# NN22_VCCS_SrcAdapter02_s00.net
KiCad netlist of a schematic drawn in EAGLE
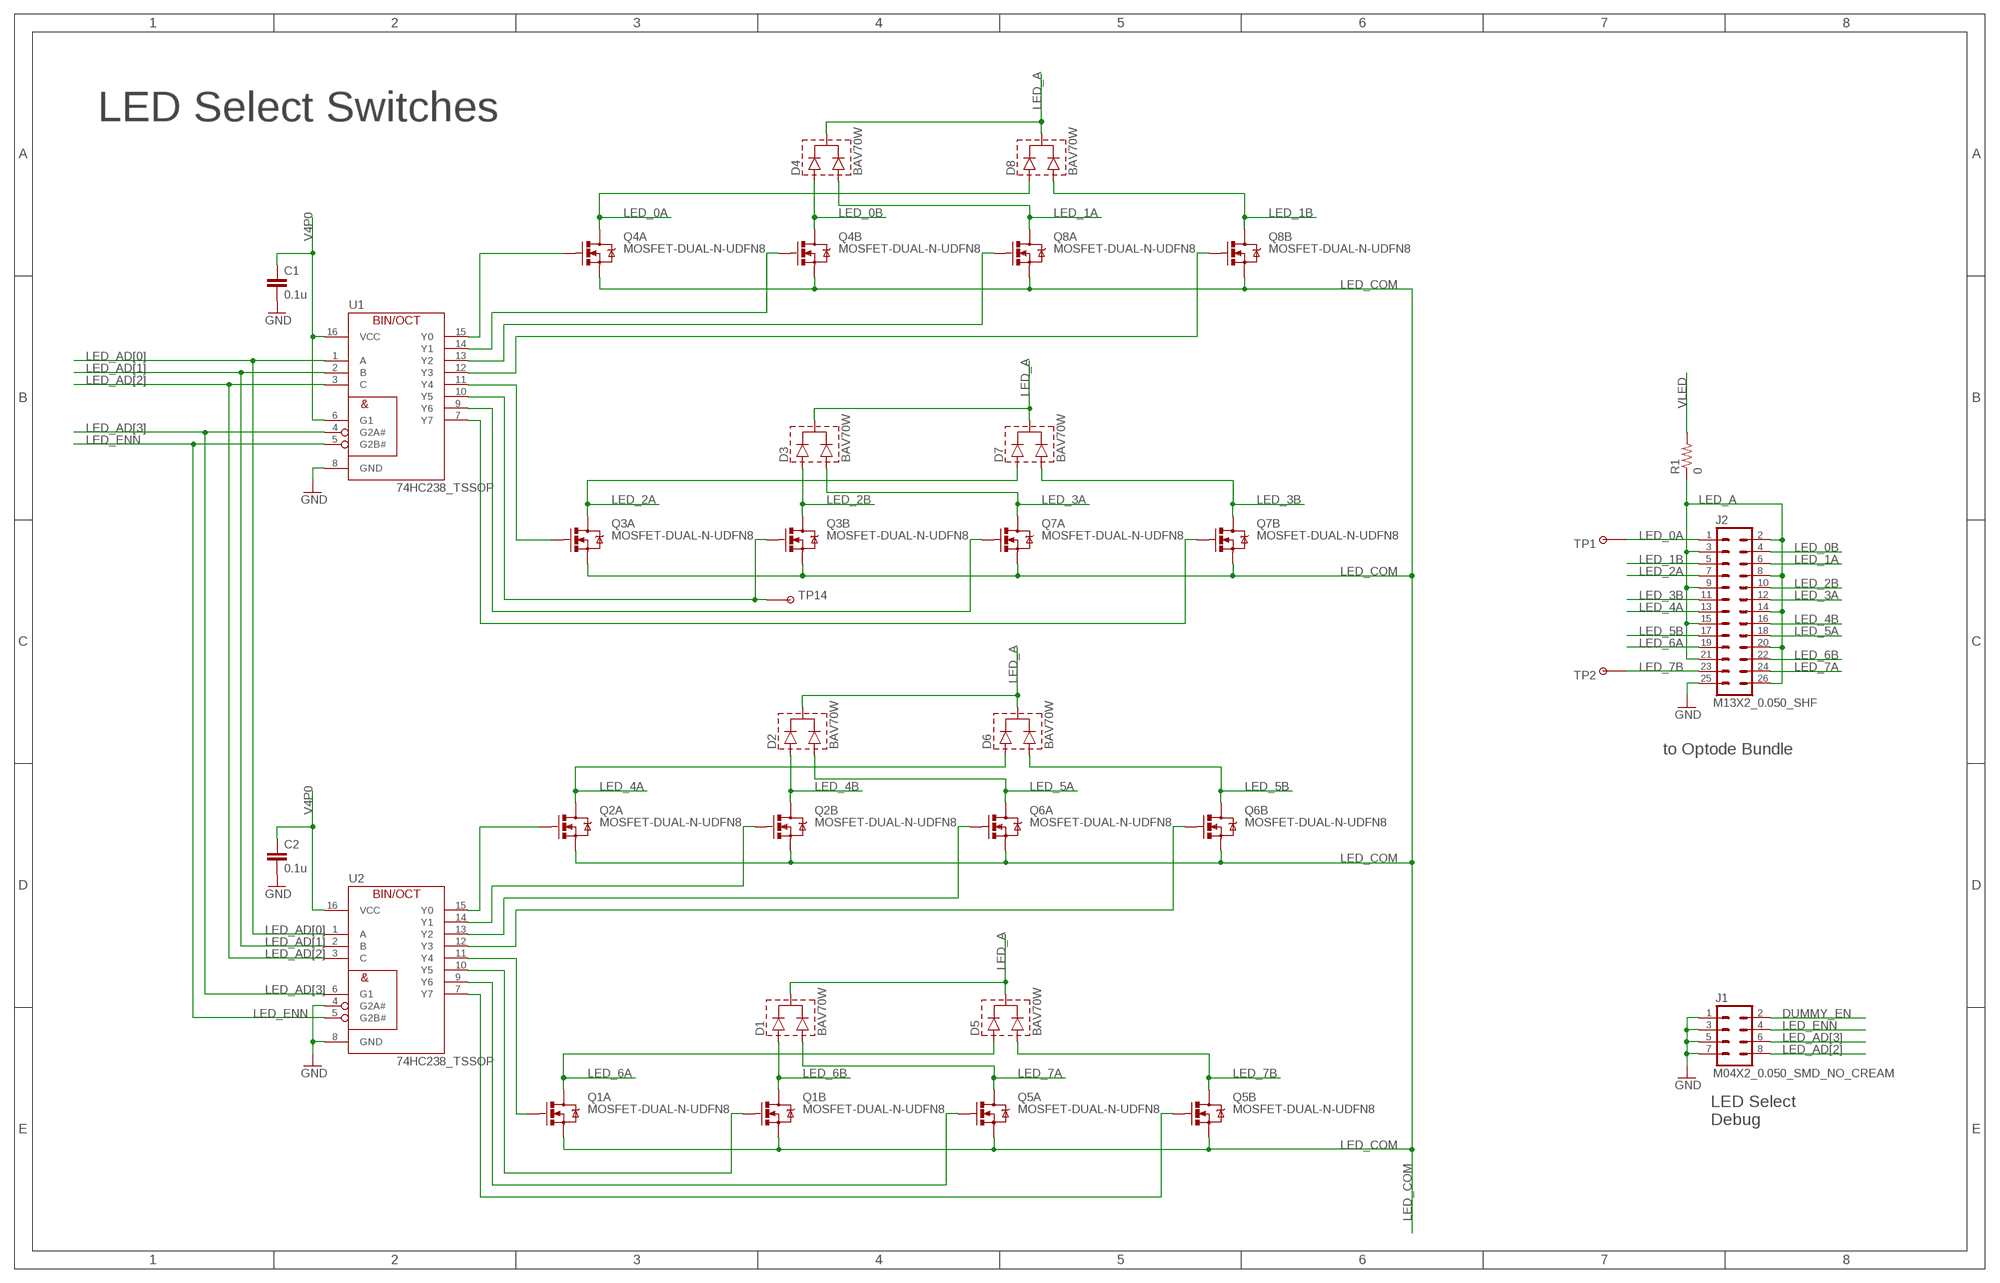
[diagram p0: schematic, sheet 1]
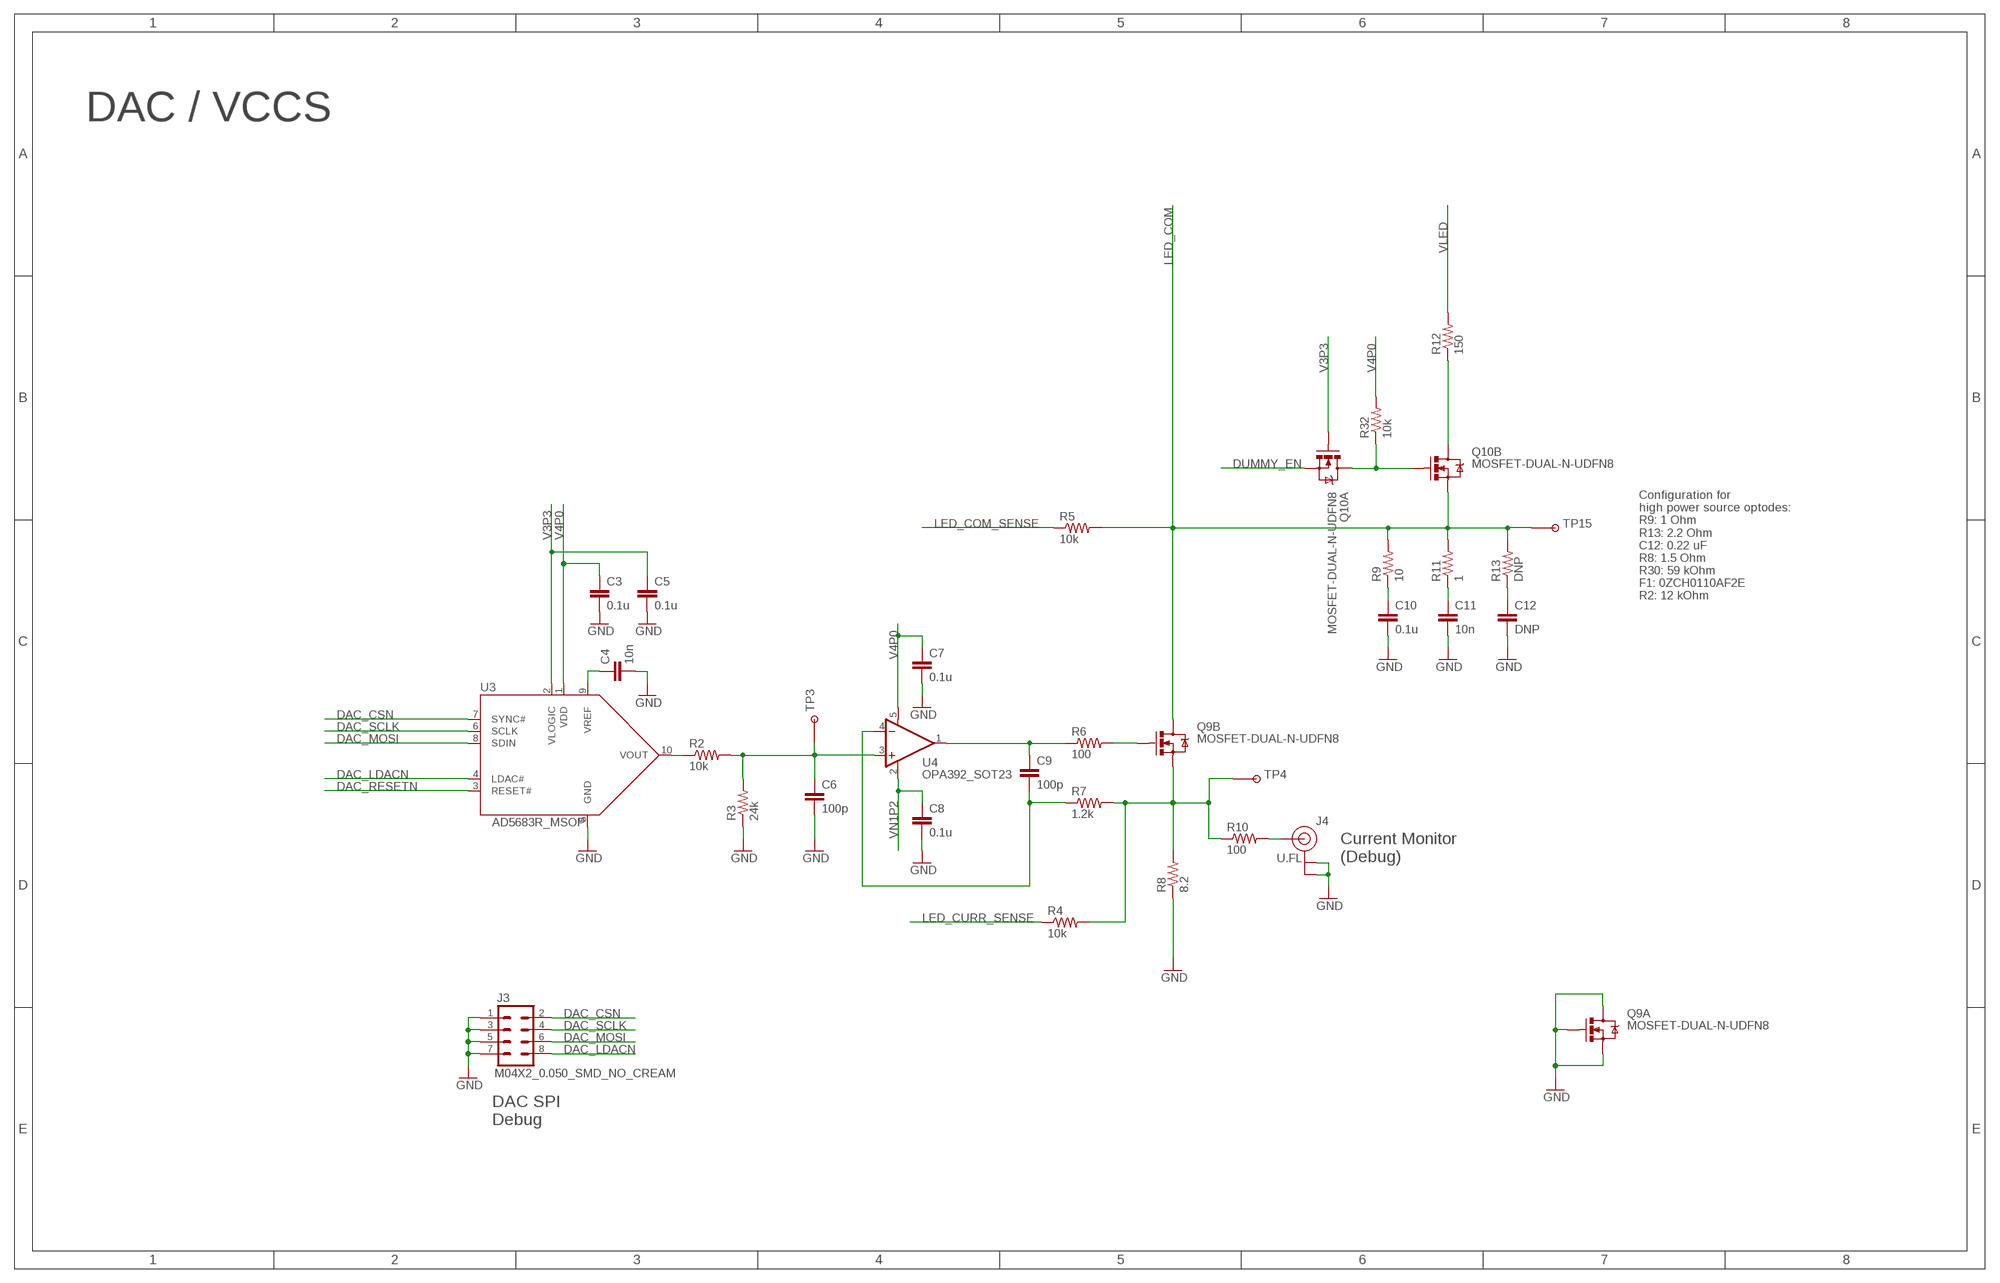
[diagram p1: schematic, sheet 2]
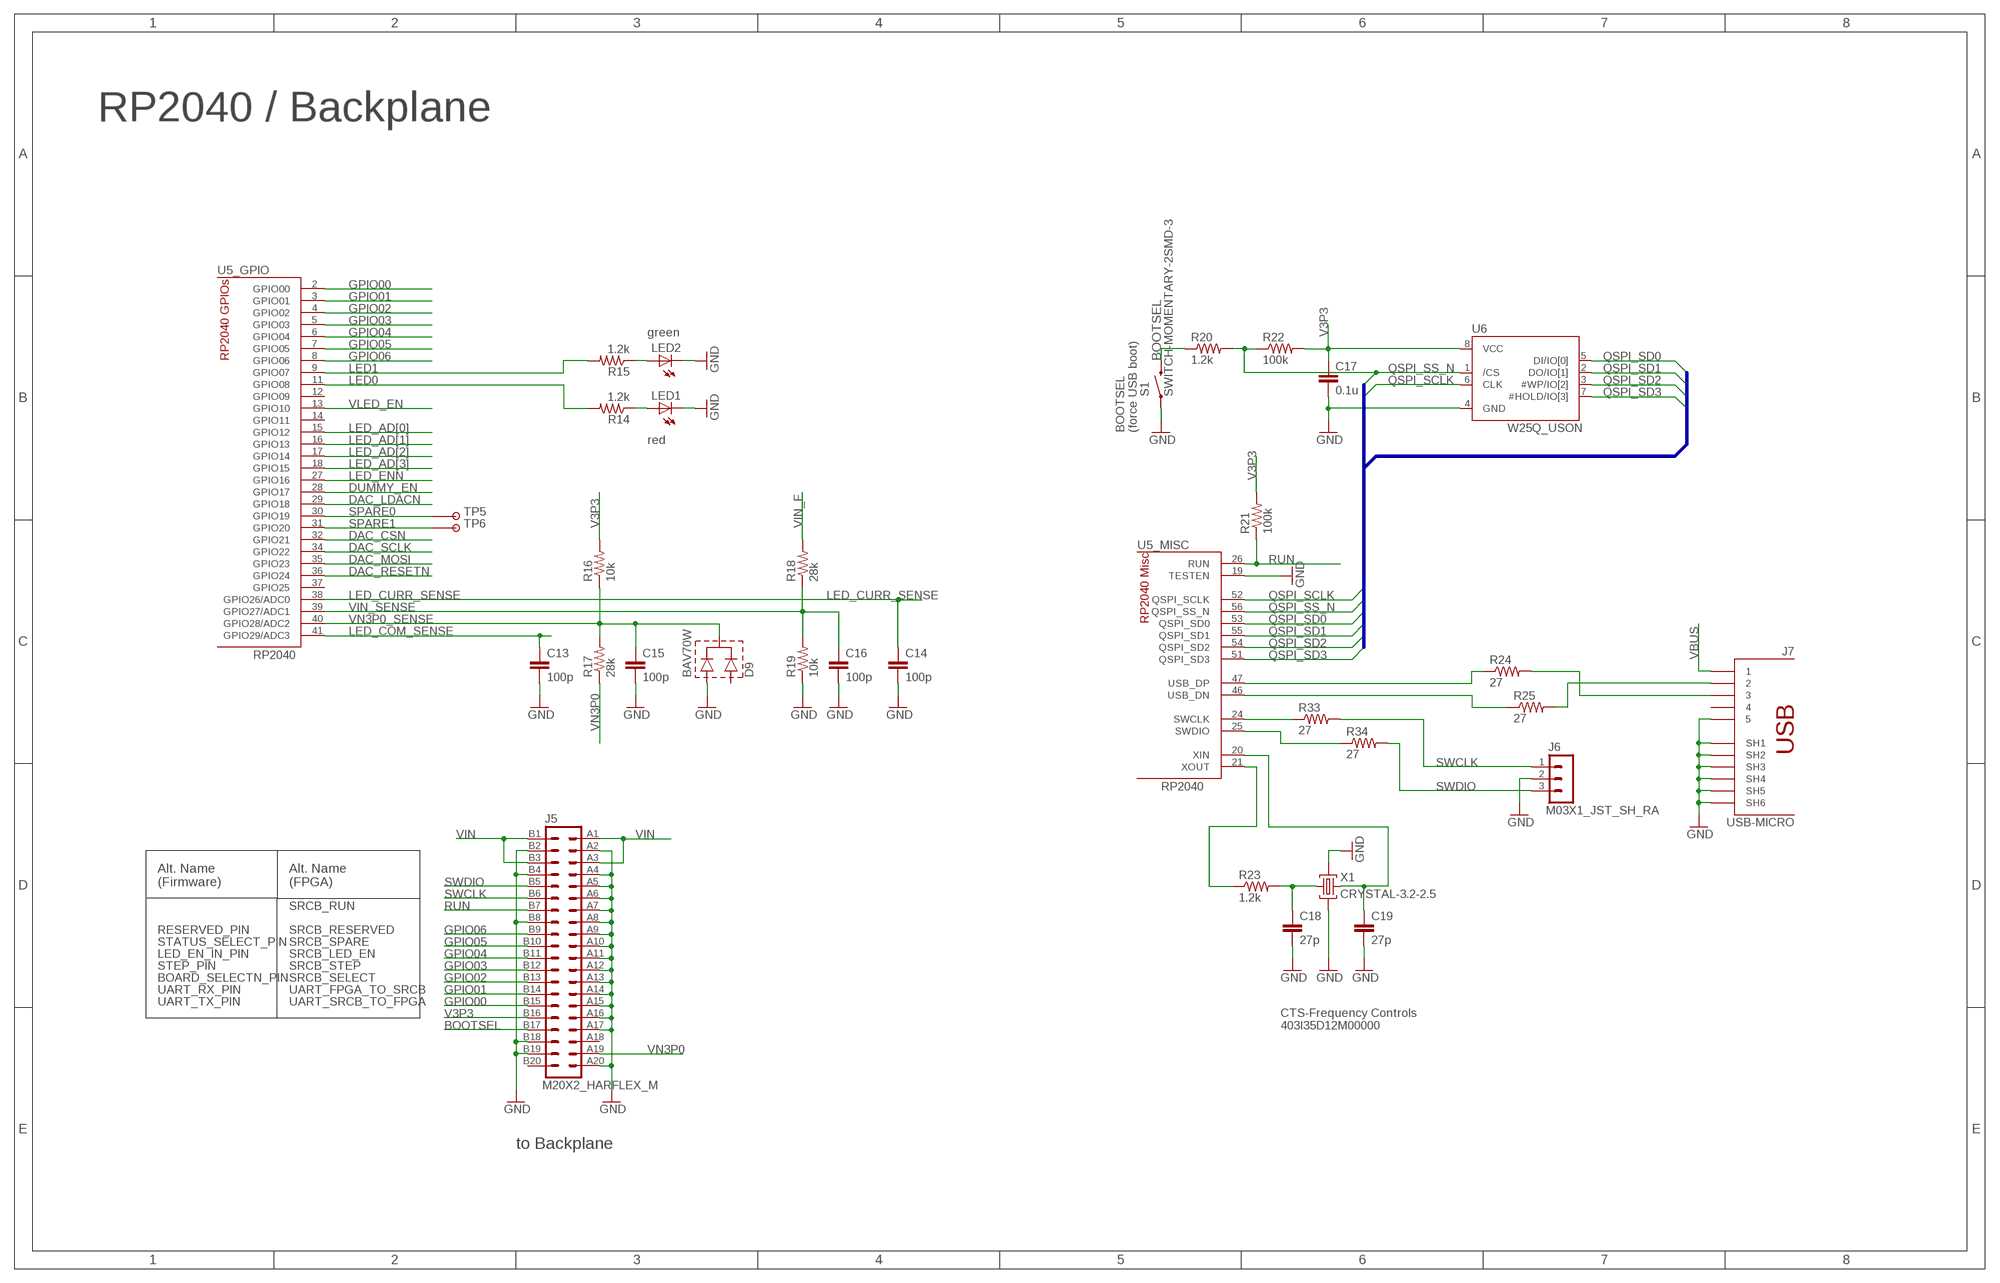
[diagram p2: schematic, sheet 3]
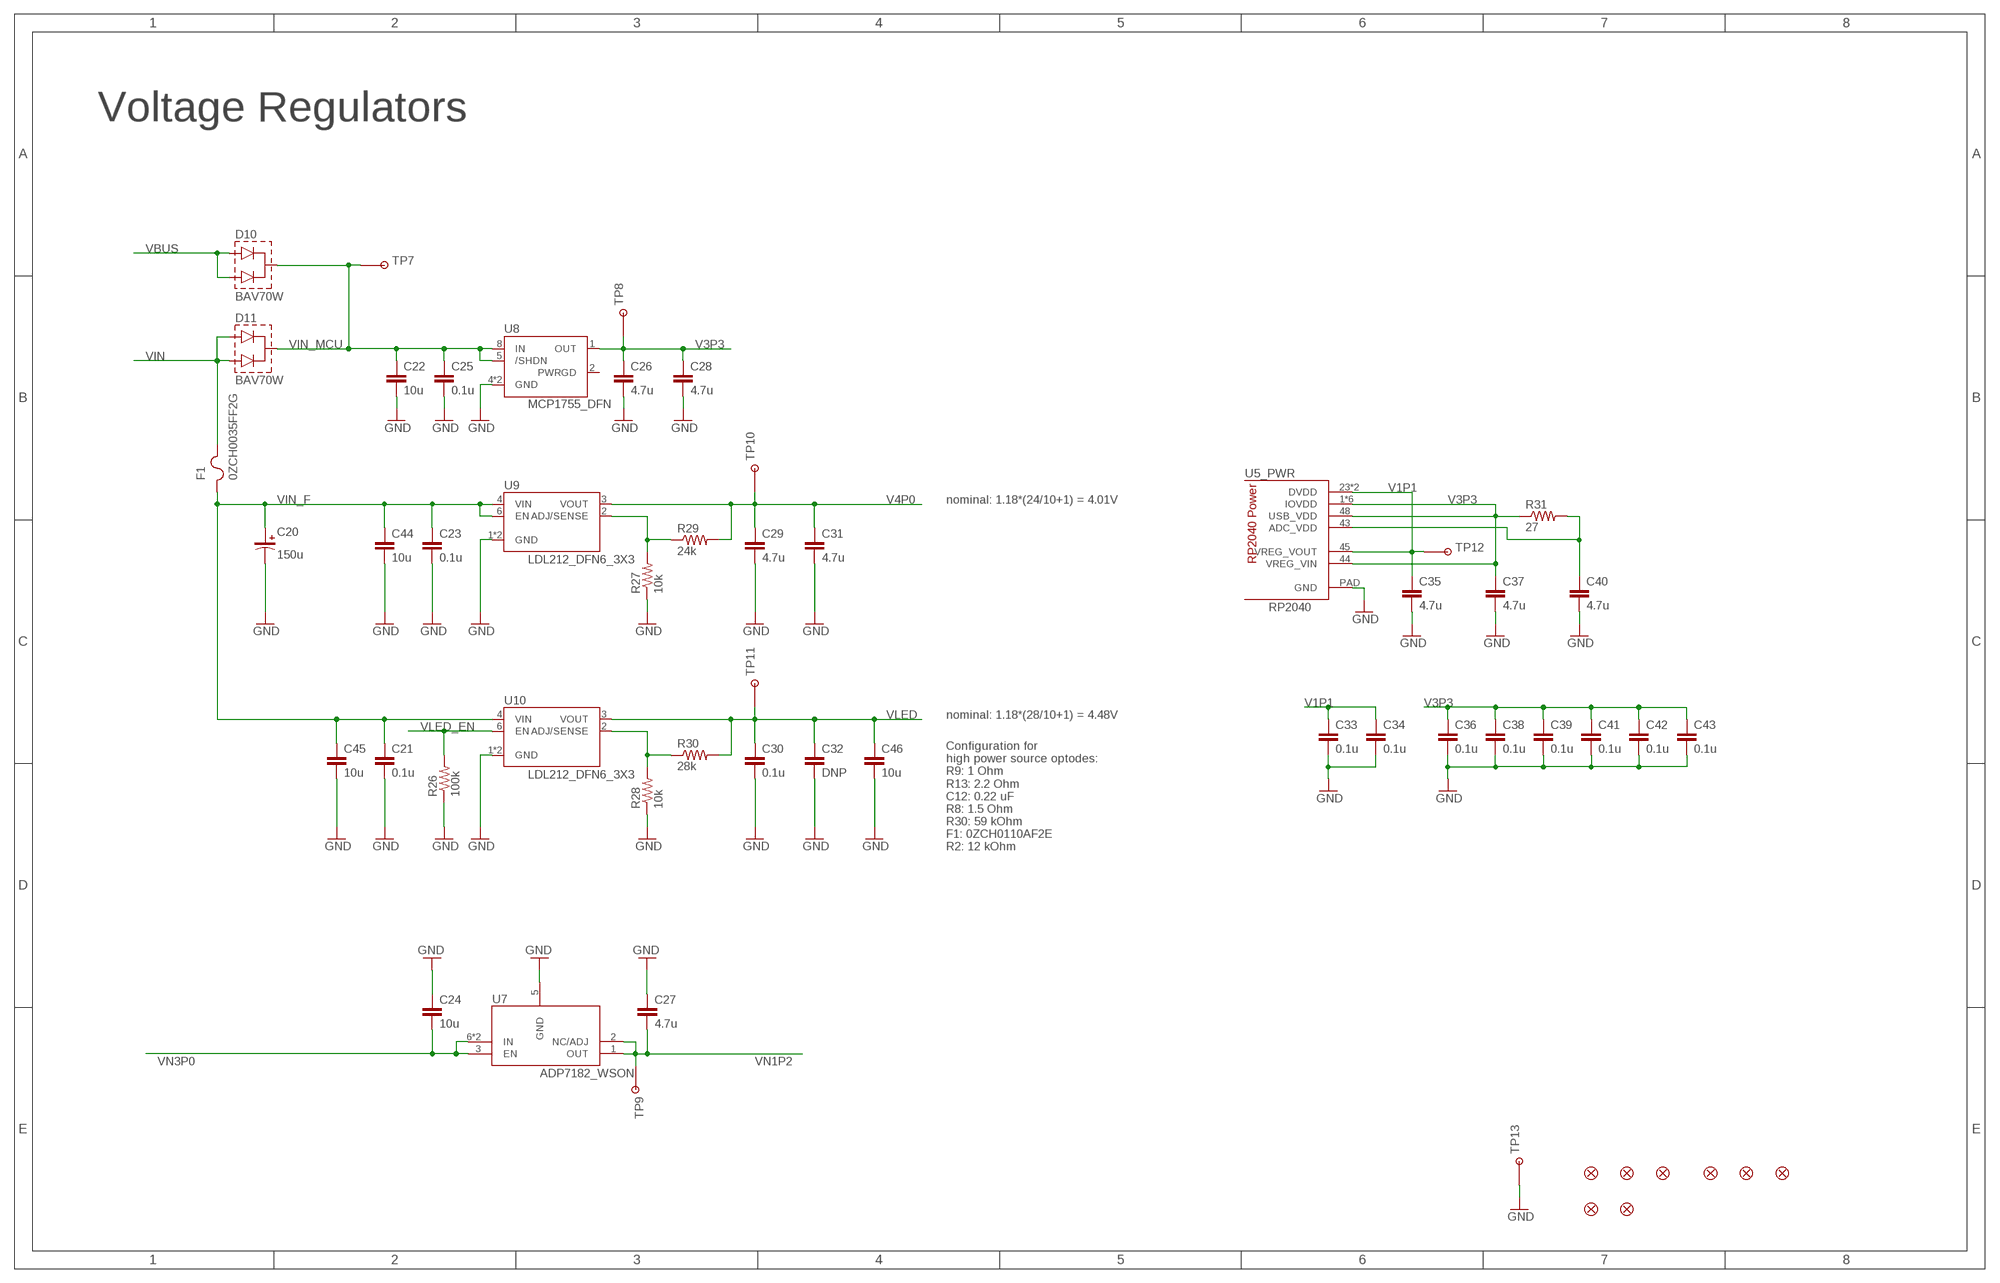
[diagram p3: schematic, sheet 4]

(export (version "E")
  (design (tool "Eeschema 10.0.6"))
  (components
    (comp (ref "C20")
      (value "150u")
      (footprint "eagle-import:2917-CAP")
      (libsource (lib "eagle-import") (part "CAP-POL2917"))
    )
    (comp (ref "C21")
      (value "0.1u")
      (footprint "eagle-import:0402-CAP")
      (libsource (lib "eagle-import") (part "CAP0402-CAP"))
    )
    (comp (ref "C22")
      (value "10u")
      (footprint "eagle-import:0603-CAP")
      (libsource (lib "eagle-import") (part "CAP0603-CAP"))
    )
    (comp (ref "C23")
      (value "0.1u")
      (footprint "eagle-import:0402-CAP")
      (libsource (lib "eagle-import") (part "CAP0402-CAP"))
    )
    (comp (ref "C24")
      (value "10u")
      (footprint "eagle-import:0603-CAP")
      (libsource (lib "eagle-import") (part "CAP0603-CAP"))
    )
    (comp (ref "C25")
      (value "0.1u")
      (footprint "eagle-import:0402-CAP")
      (libsource (lib "eagle-import") (part "CAP0402-CAP"))
    )
    (comp (ref "C26")
      (value "4.7u")
      (footprint "eagle-import:0402-CAP")
      (libsource (lib "eagle-import") (part "CAP0402-CAP"))
    )
    (comp (ref "C27")
      (value "4.7u")
      (footprint "eagle-import:0402-CAP")
      (libsource (lib "eagle-import") (part "CAP0402-CAP"))
    )
    (comp (ref "C28")
      (value "4.7u")
      (footprint "eagle-import:0402-CAP")
      (libsource (lib "eagle-import") (part "CAP0402-CAP"))
    )
    (comp (ref "C29")
      (value "4.7u")
      (footprint "eagle-import:0402-CAP")
      (libsource (lib "eagle-import") (part "CAP0402-CAP"))
    )
    (comp (ref "C30")
      (value "0.1u")
      (footprint "eagle-import:0402-CAP")
      (libsource (lib "eagle-import") (part "CAP0402-CAP"))
    )
    (comp (ref "C31")
      (value "4.7u")
      (footprint "eagle-import:0402-CAP")
      (libsource (lib "eagle-import") (part "CAP0402-CAP"))
    )
    (comp (ref "C32")
      (value "DNP")
      (footprint "eagle-import:0402-CAP")
      (libsource (lib "eagle-import") (part "CAP0402-CAP"))
    )
    (comp (ref "C33")
      (value "0.1u")
      (footprint "eagle-import:0402-CAP")
      (libsource (lib "eagle-import") (part "CAP0402-CAP"))
    )
    (comp (ref "C34")
      (value "0.1u")
      (footprint "eagle-import:0402-CAP")
      (libsource (lib "eagle-import") (part "CAP0402-CAP"))
    )
    (comp (ref "C35")
      (value "4.7u")
      (footprint "eagle-import:0402-CAP")
      (libsource (lib "eagle-import") (part "CAP0402-CAP"))
    )
    (comp (ref "C36")
      (value "0.1u")
      (footprint "eagle-import:0402-CAP")
      (libsource (lib "eagle-import") (part "CAP0402-CAP"))
    )
    (comp (ref "C37")
      (value "4.7u")
      (footprint "eagle-import:0402-CAP")
      (libsource (lib "eagle-import") (part "CAP0402-CAP"))
    )
    (comp (ref "C38")
      (value "0.1u")
      (footprint "eagle-import:0402-CAP")
      (libsource (lib "eagle-import") (part "CAP0402-CAP"))
    )
    (comp (ref "C39")
      (value "0.1u")
      (footprint "eagle-import:0402-CAP")
      (libsource (lib "eagle-import") (part "CAP0402-CAP"))
    )
    (comp (ref "C40")
      (value "4.7u")
      (footprint "eagle-import:0402-CAP")
      (libsource (lib "eagle-import") (part "CAP0402-CAP"))
    )
    (comp (ref "C41")
      (value "0.1u")
      (footprint "eagle-import:0402-CAP")
      (libsource (lib "eagle-import") (part "CAP0402-CAP"))
    )
    (comp (ref "C42")
      (value "0.1u")
      (footprint "eagle-import:0402-CAP")
      (libsource (lib "eagle-import") (part "CAP0402-CAP"))
    )
    (comp (ref "C43")
      (value "0.1u")
      (footprint "eagle-import:0402-CAP")
      (libsource (lib "eagle-import") (part "CAP0402-CAP"))
    )
    (comp (ref "C44")
      (value "10u")
      (footprint "eagle-import:0603-CAP")
      (libsource (lib "eagle-import") (part "CAP0603-CAP"))
    )
    (comp (ref "C45")
      (value "10u")
      (footprint "eagle-import:0603-CAP")
      (libsource (lib "eagle-import") (part "CAP0603-CAP"))
    )
    (comp (ref "C46")
      (value "10u")
      (footprint "eagle-import:0603-CAP")
      (libsource (lib "eagle-import") (part "CAP0603-CAP"))
    )
    (comp (ref "D10")
      (value "BAV70W")
      (footprint "eagle-import:SOT323")
      (libsource (lib "eagle-import") (part "DIODE-COMMON_CATHODE_SOT323"))
    )
    (comp (ref "D11")
      (value "BAV70W")
      (footprint "eagle-import:SOT323")
      (libsource (lib "eagle-import") (part "DIODE-COMMON_CATHODE_SOT323"))
    )
    (comp (ref "F1")
      (value "0ZCH0035FF2G")
      (footprint "eagle-import:1210-FUSE")
      (libsource (lib "eagle-import") (part "FUSE_1210"))
    )
    (comp (ref "FID1")
      (value "FIDUCIALUFIDUCIAL")
      (footprint "eagle-import:MICRO-FIDUCIAL")
      (libsource (lib "eagle-import") (part "FIDUCIALUFIDUCIAL"))
    )
    (comp (ref "FID2")
      (value "FIDUCIALUFIDUCIAL")
      (footprint "eagle-import:MICRO-FIDUCIAL")
      (libsource (lib "eagle-import") (part "FIDUCIALUFIDUCIAL"))
    )
    (comp (ref "FID3")
      (value "FIDUCIALUFIDUCIAL")
      (footprint "eagle-import:MICRO-FIDUCIAL")
      (libsource (lib "eagle-import") (part "FIDUCIALUFIDUCIAL"))
    )
    (comp (ref "FID4")
      (value "FIDUCIALUFIDUCIAL")
      (footprint "eagle-import:MICRO-FIDUCIAL")
      (libsource (lib "eagle-import") (part "FIDUCIALUFIDUCIAL"))
    )
    (comp (ref "FID5")
      (value "FIDUCIALUFIDUCIAL")
      (footprint "eagle-import:MICRO-FIDUCIAL")
      (libsource (lib "eagle-import") (part "FIDUCIALUFIDUCIAL"))
    )
    (comp (ref "FID6")
      (value "FIDUCIALUFIDUCIAL")
      (footprint "eagle-import:MICRO-FIDUCIAL")
      (libsource (lib "eagle-import") (part "FIDUCIALUFIDUCIAL"))
    )
    (comp (ref "FID7")
      (value "FIDUCIALUFIDUCIAL")
      (footprint "eagle-import:MICRO-FIDUCIAL")
      (libsource (lib "eagle-import") (part "FIDUCIALUFIDUCIAL"))
    )
    (comp (ref "FID8")
      (value "FIDUCIALUFIDUCIAL")
      (footprint "eagle-import:MICRO-FIDUCIAL")
      (libsource (lib "eagle-import") (part "FIDUCIALUFIDUCIAL"))
    )
    (comp (ref "R26")
      (value "100k")
      (footprint "eagle-import:0402-RES")
      (libsource (lib "eagle-import") (part "RESISTOR0402-RES"))
    )
    (comp (ref "R27")
      (value "10k")
      (footprint "eagle-import:0402-RES")
      (libsource (lib "eagle-import") (part "RESISTOR0402-RES"))
    )
    (comp (ref "R28")
      (value "10k")
      (footprint "eagle-import:0402-RES")
      (libsource (lib "eagle-import") (part "RESISTOR0402-RES"))
    )
    (comp (ref "R29")
      (value "24k")
      (footprint "eagle-import:0402-RES")
      (libsource (lib "eagle-import") (part "RESISTOR0402-RES"))
    )
    (comp (ref "R30")
      (value "28k")
      (footprint "eagle-import:0402-RES")
      (libsource (lib "eagle-import") (part "RESISTOR0402-RES"))
    )
    (comp (ref "R31")
      (value "27")
      (footprint "eagle-import:0402-RES")
      (libsource (lib "eagle-import") (part "RESISTOR0402-RES"))
    )
    (comp (ref "TP7")
      (value "TESTPOINT_ROUND")
      (footprint "eagle-import:TESTPAD_ROUND")
      (libsource (lib "eagle-import") (part "TESTPOINT_ROUND"))
    )
    (comp (ref "TP8")
      (value "TESTPOINT_ROUND")
      (footprint "eagle-import:TESTPAD_ROUND")
      (libsource (lib "eagle-import") (part "TESTPOINT_ROUND"))
    )
    (comp (ref "TP9")
      (value "TESTPOINT_ROUND")
      (footprint "eagle-import:TESTPAD_ROUND")
      (libsource (lib "eagle-import") (part "TESTPOINT_ROUND"))
    )
    (comp (ref "TP10")
      (value "TESTPOINT_ROUND")
      (footprint "eagle-import:TESTPAD_ROUND")
      (libsource (lib "eagle-import") (part "TESTPOINT_ROUND"))
    )
    (comp (ref "TP11")
      (value "TESTPOINT_ROUND")
      (footprint "eagle-import:TESTPAD_ROUND")
      (libsource (lib "eagle-import") (part "TESTPOINT_ROUND"))
    )
    (comp (ref "TP12")
      (value "TESTPOINTPADSMALL")
      (footprint "eagle-import:TESTPAD_SMALL")
      (libsource (lib "eagle-import") (part "TESTPOINTPADSMALL"))
    )
    (comp (ref "TP13")
      (value "TESTPOINT1X01")
      (footprint "eagle-import:1X01")
      (libsource (lib "eagle-import") (part "TESTPOINT1X01"))
    )
    (comp (ref "U5")
      (value "RP2040")
      (footprint "eagle-import:QFN-56_EP")
      (libsource (lib "eagle-import") (part "RP2040"))
    )
    (comp (ref "U7")
      (value "ADP7182_WSON")
      (footprint "eagle-import:WSON6")
      (libsource (lib "eagle-import") (part "ADP7182_WSON"))
    )
    (comp (ref "U8")
      (value "MCP1755_DFN")
      (footprint "eagle-import:DFN8_2X3MM")
      (libsource (lib "eagle-import") (part "MCP1755_DFN"))
    )
    (comp (ref "U9")
      (value "LDL212_DFN6_3X3")
      (footprint "eagle-import:DFN6_3X3MM")
      (libsource (lib "eagle-import") (part "LDL212_DFN6_3X3"))
    )
    (comp (ref "U10")
      (value "LDL212_DFN6_3X3")
      (footprint "eagle-import:DFN6_3X3MM")
      (libsource (lib "eagle-import") (part "LDL212_DFN6_3X3"))
    )
    (comp (ref "C3")
      (value "0.1u")
      (footprint "eagle-import:0402-CAP")
      (libsource (lib "eagle-import") (part "CAP0402-CAP"))
    )
    (comp (ref "C4")
      (value "10n")
      (footprint "eagle-import:0402-CAP")
      (libsource (lib "eagle-import") (part "CAP0402-CAP"))
    )
    (comp (ref "C5")
      (value "0.1u")
      (footprint "eagle-import:0402-CAP")
      (libsource (lib "eagle-import") (part "CAP0402-CAP"))
    )
    (comp (ref "C6")
      (value "100p")
      (footprint "eagle-import:0402-CAP")
      (libsource (lib "eagle-import") (part "CAP0402-CAP"))
    )
    (comp (ref "C7")
      (value "0.1u")
      (footprint "eagle-import:0402-CAP")
      (libsource (lib "eagle-import") (part "CAP0402-CAP"))
    )
    (comp (ref "C8")
      (value "0.1u")
      (footprint "eagle-import:0402-CAP")
      (libsource (lib "eagle-import") (part "CAP0402-CAP"))
    )
    (comp (ref "C9")
      (value "100p")
      (footprint "eagle-import:0402-CAP")
      (libsource (lib "eagle-import") (part "CAP0402-CAP"))
    )
    (comp (ref "C10")
      (value "0.1u")
      (footprint "eagle-import:0402-CAP")
      (libsource (lib "eagle-import") (part "CAP0402-CAP"))
    )
    (comp (ref "C11")
      (value "10n")
      (footprint "eagle-import:0402-CAP")
      (libsource (lib "eagle-import") (part "CAP0402-CAP"))
    )
    (comp (ref "C12")
      (value "DNP")
      (footprint "eagle-import:0603-CAP")
      (libsource (lib "eagle-import") (part "CAP0603-CAP"))
    )
    (comp (ref "J3")
      (value "M04X2_0.050_SMD_NO_CREAM")
      (footprint "eagle-import:M04X2_0.050_SMD_NO_CREAM")
      (libsource (lib "eagle-import") (part "M04X2_0.050_SMD_NO_CREAM"))
    )
    (comp (ref "J4")
      (value "U.FL")
      (footprint "eagle-import:U.FL")
      (libsource (lib "eagle-import") (part "U.FL"))
    )
    (comp (ref "Q9")
      (value "MOSFET-DUAL-N-UDFN8")
      (footprint "eagle-import:UDFN8")
      (libsource (lib "eagle-import") (part "MOSFET-DUAL-N-UDFN8"))
    )
    (comp (ref "Q10")
      (value "MOSFET-DUAL-N-UDFN8")
      (footprint "eagle-import:UDFN8")
      (libsource (lib "eagle-import") (part "MOSFET-DUAL-N-UDFN8"))
    )
    (comp (ref "R2")
      (value "10k")
      (footprint "eagle-import:0402-RES")
      (libsource (lib "eagle-import") (part "RESISTOR0402-RES"))
    )
    (comp (ref "R3")
      (value "24k")
      (footprint "eagle-import:0402-RES")
      (libsource (lib "eagle-import") (part "RESISTOR0402-RES"))
    )
    (comp (ref "R4")
      (value "10k")
      (footprint "eagle-import:0402-RES")
      (libsource (lib "eagle-import") (part "RESISTOR0402-RES"))
    )
    (comp (ref "R5")
      (value "10k")
      (footprint "eagle-import:0402-RES")
      (libsource (lib "eagle-import") (part "RESISTOR0402-RES"))
    )
    (comp (ref "R6")
      (value "100")
      (footprint "eagle-import:0402-RES")
      (libsource (lib "eagle-import") (part "RESISTOR0402-RES"))
    )
    (comp (ref "R7")
      (value "1.2k")
      (footprint "eagle-import:0402-RES")
      (libsource (lib "eagle-import") (part "RESISTOR0402-RES"))
    )
    (comp (ref "R8")
      (value "8.2")
      (footprint "eagle-import:R2512")
      (libsource (lib "eagle-import") (part "RESISTOR2512"))
    )
    (comp (ref "R9")
      (value "10")
      (footprint "eagle-import:0603-RES")
      (libsource (lib "eagle-import") (part "RESISTOR0603-RES"))
    )
    (comp (ref "R10")
      (value "100")
      (footprint "eagle-import:0402-RES")
      (libsource (lib "eagle-import") (part "RESISTOR0402-RES"))
    )
    (comp (ref "R11")
      (value "1")
      (footprint "eagle-import:0603-RES")
      (libsource (lib "eagle-import") (part "RESISTOR0603-RES"))
    )
    (comp (ref "R12")
      (value "150")
      (footprint "eagle-import:0603-RES")
      (libsource (lib "eagle-import") (part "RESISTOR0603-RES"))
    )
    (comp (ref "R13")
      (value "DNP")
      (footprint "eagle-import:0603-RES")
      (libsource (lib "eagle-import") (part "RESISTOR0603-RES"))
    )
    (comp (ref "R32")
      (value "10k")
      (footprint "eagle-import:0402-RES")
      (libsource (lib "eagle-import") (part "RESISTOR0402-RES"))
    )
    (comp (ref "TP3")
      (value "TESTPOINT_ROUND")
      (footprint "eagle-import:TESTPAD_ROUND")
      (libsource (lib "eagle-import") (part "TESTPOINT_ROUND"))
    )
    (comp (ref "TP4")
      (value "TESTPOINT_ROUND")
      (footprint "eagle-import:TESTPAD_ROUND")
      (libsource (lib "eagle-import") (part "TESTPOINT_ROUND"))
    )
    (comp (ref "TP15")
      (value "TESTPOINT_ROUND")
      (footprint "eagle-import:TESTPAD_ROUND")
      (libsource (lib "eagle-import") (part "TESTPOINT_ROUND"))
    )
    (comp (ref "U3")
      (value "AD5683R_MSOP")
      (footprint "eagle-import:MSOP10")
      (libsource (lib "eagle-import") (part "AD5683R_MSOP"))
    )
    (comp (ref "U4")
      (value "OPA392_SOT23")
      (footprint "eagle-import:SOT23-5")
      (libsource (lib "eagle-import") (part "OPA392_SOT23"))
    )
    (comp (ref "C1")
      (value "0.1u")
      (footprint "eagle-import:0402-CAP")
      (libsource (lib "eagle-import") (part "CAP0402-CAP"))
    )
    (comp (ref "C2")
      (value "0.1u")
      (footprint "eagle-import:0402-CAP")
      (libsource (lib "eagle-import") (part "CAP0402-CAP"))
    )
    (comp (ref "D1")
      (value "BAV70W")
      (footprint "eagle-import:SOT323")
      (libsource (lib "eagle-import") (part "DIODE-COMMON_CATHODE_SOT323"))
    )
    (comp (ref "D2")
      (value "BAV70W")
      (footprint "eagle-import:SOT323")
      (libsource (lib "eagle-import") (part "DIODE-COMMON_CATHODE_SOT323"))
    )
    (comp (ref "D3")
      (value "BAV70W")
      (footprint "eagle-import:SOT323")
      (libsource (lib "eagle-import") (part "DIODE-COMMON_CATHODE_SOT323"))
    )
    (comp (ref "D4")
      (value "BAV70W")
      (footprint "eagle-import:SOT323")
      (libsource (lib "eagle-import") (part "DIODE-COMMON_CATHODE_SOT323"))
    )
    (comp (ref "D5")
      (value "BAV70W")
      (footprint "eagle-import:SOT323")
      (libsource (lib "eagle-import") (part "DIODE-COMMON_CATHODE_SOT323"))
    )
    (comp (ref "D6")
      (value "BAV70W")
      (footprint "eagle-import:SOT323")
      (libsource (lib "eagle-import") (part "DIODE-COMMON_CATHODE_SOT323"))
    )
    (comp (ref "D7")
      (value "BAV70W")
      (footprint "eagle-import:SOT323")
      (libsource (lib "eagle-import") (part "DIODE-COMMON_CATHODE_SOT323"))
    )
    (comp (ref "D8")
      (value "BAV70W")
      (footprint "eagle-import:SOT323")
      (libsource (lib "eagle-import") (part "DIODE-COMMON_CATHODE_SOT323"))
    )
    (comp (ref "J1")
      (value "M04X2_0.050_SMD_NO_CREAM")
      (footprint "eagle-import:M04X2_0.050_SMD_NO_CREAM")
      (libsource (lib "eagle-import") (part "M04X2_0.050_SMD_NO_CREAM"))
    )
    (comp (ref "J2")
      (value "M13X2_0.050_SHF")
      (footprint "eagle-import:M13X2_0.050_SHF")
      (libsource (lib "eagle-import") (part "M13X2_0.050_SHF"))
    )
    (comp (ref "Q1")
      (value "MOSFET-DUAL-N-UDFN8")
      (footprint "eagle-import:UDFN8")
      (libsource (lib "eagle-import") (part "MOSFET-DUAL-N-UDFN8"))
    )
    (comp (ref "Q2")
      (value "MOSFET-DUAL-N-UDFN8")
      (footprint "eagle-import:UDFN8")
      (libsource (lib "eagle-import") (part "MOSFET-DUAL-N-UDFN8"))
    )
    (comp (ref "Q3")
      (value "MOSFET-DUAL-N-UDFN8")
      (footprint "eagle-import:UDFN8")
      (libsource (lib "eagle-import") (part "MOSFET-DUAL-N-UDFN8"))
    )
    (comp (ref "Q4")
      (value "MOSFET-DUAL-N-UDFN8")
      (footprint "eagle-import:UDFN8")
      (libsource (lib "eagle-import") (part "MOSFET-DUAL-N-UDFN8"))
    )
    (comp (ref "Q5")
      (value "MOSFET-DUAL-N-UDFN8")
      (footprint "eagle-import:UDFN8")
      (libsource (lib "eagle-import") (part "MOSFET-DUAL-N-UDFN8"))
    )
    (comp (ref "Q6")
      (value "MOSFET-DUAL-N-UDFN8")
      (footprint "eagle-import:UDFN8")
      (libsource (lib "eagle-import") (part "MOSFET-DUAL-N-UDFN8"))
    )
    (comp (ref "Q7")
      (value "MOSFET-DUAL-N-UDFN8")
      (footprint "eagle-import:UDFN8")
      (libsource (lib "eagle-import") (part "MOSFET-DUAL-N-UDFN8"))
    )
    (comp (ref "Q8")
      (value "MOSFET-DUAL-N-UDFN8")
      (footprint "eagle-import:UDFN8")
      (libsource (lib "eagle-import") (part "MOSFET-DUAL-N-UDFN8"))
    )
    (comp (ref "R1")
      (value "0")
      (footprint "eagle-import:1206")
      (libsource (lib "eagle-import") (part "RESISTOR1206"))
    )
    (comp (ref "TP1")
      (value "TESTPOINT_ROUND")
      (footprint "eagle-import:TESTPAD_ROUND")
      (libsource (lib "eagle-import") (part "TESTPOINT_ROUND"))
    )
    (comp (ref "TP2")
      (value "TESTPOINT_ROUND")
      (footprint "eagle-import:TESTPAD_ROUND")
      (libsource (lib "eagle-import") (part "TESTPOINT_ROUND"))
    )
    (comp (ref "TP14")
      (value "TESTPOINTPADSMALL")
      (footprint "eagle-import:TESTPAD_SMALL")
      (libsource (lib "eagle-import") (part "TESTPOINTPADSMALL"))
    )
    (comp (ref "U1")
      (value "74HC238_TSSOP")
      (footprint "eagle-import:TSSOP16")
      (libsource (lib "eagle-import") (part "74HC238_TSSOP"))
    )
    (comp (ref "U2")
      (value "74HC238_TSSOP")
      (footprint "eagle-import:TSSOP16")
      (libsource (lib "eagle-import") (part "74HC238_TSSOP"))
    )
    (comp (ref "C13")
      (value "100p")
      (footprint "eagle-import:0402-CAP")
      (libsource (lib "eagle-import") (part "CAP0402-CAP"))
    )
    (comp (ref "C14")
      (value "100p")
      (footprint "eagle-import:0402-CAP")
      (libsource (lib "eagle-import") (part "CAP0402-CAP"))
    )
    (comp (ref "C15")
      (value "100p")
      (footprint "eagle-import:0402-CAP")
      (libsource (lib "eagle-import") (part "CAP0402-CAP"))
    )
    (comp (ref "C16")
      (value "100p")
      (footprint "eagle-import:0402-CAP")
      (libsource (lib "eagle-import") (part "CAP0402-CAP"))
    )
    (comp (ref "C17")
      (value "0.1u")
      (footprint "eagle-import:0402-CAP")
      (libsource (lib "eagle-import") (part "CAP0402-CAP"))
    )
    (comp (ref "C18")
      (value "27p")
      (footprint "eagle-import:0402-CAP")
      (libsource (lib "eagle-import") (part "CAP0402-CAP"))
    )
    (comp (ref "C19")
      (value "27p")
      (footprint "eagle-import:0402-CAP")
      (libsource (lib "eagle-import") (part "CAP0402-CAP"))
    )
    (comp (ref "D9")
      (value "BAV70W")
      (footprint "eagle-import:SOT323")
      (libsource (lib "eagle-import") (part "DIODE-COMMON_CATHODE_SOT323"))
    )
    (comp (ref "J5")
      (value "M20X2_HARFLEX_M")
      (footprint "eagle-import:M20X2_HARFLEX_M")
      (libsource (lib "eagle-import") (part "M20X2_HARFLEX_M"))
    )
    (comp (ref "J6")
      (value "M03X1_JST_SH_RA")
      (footprint "eagle-import:M03X1_JST_SH_SM_RA")
      (libsource (lib "eagle-import") (part "M03X1_JST_SH_RA"))
    )
    (comp (ref "J7")
      (value "USB-MICRO")
      (footprint "eagle-import:USB-MICRO")
      (libsource (lib "eagle-import") (part "USB-MICRO"))
    )
    (comp (ref "LED1")
      (value "LED0603")
      (footprint "eagle-import:LED-0603")
      (libsource (lib "eagle-import") (part "LED0603"))
    )
    (comp (ref "LED2")
      (value "LED0603")
      (footprint "eagle-import:LED-0603")
      (libsource (lib "eagle-import") (part "LED0603"))
    )
    (comp (ref "R14")
      (value "1.2k")
      (footprint "eagle-import:0402-RES")
      (libsource (lib "eagle-import") (part "RESISTOR0402-RES"))
    )
    (comp (ref "R15")
      (value "1.2k")
      (footprint "eagle-import:0402-RES")
      (libsource (lib "eagle-import") (part "RESISTOR0402-RES"))
    )
    (comp (ref "R16")
      (value "10k")
      (footprint "eagle-import:0402-RES")
      (libsource (lib "eagle-import") (part "RESISTOR0402-RES"))
    )
    (comp (ref "R17")
      (value "28k")
      (footprint "eagle-import:0402-RES")
      (libsource (lib "eagle-import") (part "RESISTOR0402-RES"))
    )
    (comp (ref "R18")
      (value "28k")
      (footprint "eagle-import:0402-RES")
      (libsource (lib "eagle-import") (part "RESISTOR0402-RES"))
    )
    (comp (ref "R19")
      (value "10k")
      (footprint "eagle-import:0402-RES")
      (libsource (lib "eagle-import") (part "RESISTOR0402-RES"))
    )
    (comp (ref "R20")
      (value "1.2k")
      (footprint "eagle-import:0402-RES")
      (libsource (lib "eagle-import") (part "RESISTOR0402-RES"))
    )
    (comp (ref "R21")
      (value "100k")
      (footprint "eagle-import:0402-RES")
      (libsource (lib "eagle-import") (part "RESISTOR0402-RES"))
    )
    (comp (ref "R22")
      (value "100k")
      (footprint "eagle-import:0402-RES")
      (libsource (lib "eagle-import") (part "RESISTOR0402-RES"))
    )
    (comp (ref "R23")
      (value "1.2k")
      (footprint "eagle-import:0402-RES")
      (libsource (lib "eagle-import") (part "RESISTOR0402-RES"))
    )
    (comp (ref "R24")
      (value "27")
      (footprint "eagle-import:0402-RES")
      (libsource (lib "eagle-import") (part "RESISTOR0402-RES"))
    )
    (comp (ref "R25")
      (value "27")
      (footprint "eagle-import:0402-RES")
      (libsource (lib "eagle-import") (part "RESISTOR0402-RES"))
    )
    (comp (ref "R33")
      (value "27")
      (footprint "eagle-import:0402-RES")
      (libsource (lib "eagle-import") (part "RESISTOR0402-RES"))
    )
    (comp (ref "R34")
      (value "27")
      (footprint "eagle-import:0402-RES")
      (libsource (lib "eagle-import") (part "RESISTOR0402-RES"))
    )
    (comp (ref "S1")
      (value "SWITCH-MOMENTARY-2SMD-3")
      (footprint "eagle-import:TACTILE_SWITCH_SMD-3")
      (libsource (lib "eagle-import") (part "SWITCH-MOMENTARY-2SMD-3"))
    )
    (comp (ref "TP5")
      (value "TESTPOINTPADSMALL")
      (footprint "eagle-import:TESTPAD_SMALL")
      (libsource (lib "eagle-import") (part "TESTPOINTPADSMALL"))
    )
    (comp (ref "TP6")
      (value "TESTPOINTPADSMALL")
      (footprint "eagle-import:TESTPAD_SMALL")
      (libsource (lib "eagle-import") (part "TESTPOINTPADSMALL"))
    )
    (comp (ref "U6")
      (value "W25Q_USON")
      (footprint "eagle-import:USON8L-2X3MM")
      (libsource (lib "eagle-import") (part "W25Q_USON"))
    )
    (comp (ref "X1")
      (value "CRYSTAL-3.2-2.5")
      (footprint "eagle-import:CRYSTAL-3.2-2.5")
      (libsource (lib "eagle-import") (part "CRYSTAL-3.2-2.5"))
    )
  )
  (nets
    (net (code "1") (name "BOOTSEL") (class "Default")
      (node (ref "J5") (pin "B17") (pinfunction "33_B17") (pintype "passive"))
      (node (ref "R20") (pin "1") (pinfunction "1_1") (pintype "passive"))
      (node (ref "S1") (pin "4") (pinfunction "2_4") (pintype "passive"))
    )
    (net (code "2") (name "DAC_CSN") (class "Default")
      (node (ref "J3") (pin "2") (pinfunction "2_2") (pintype "passive"))
      (node (ref "U3") (pin "7") (pinfunction "SYNC#_7") (pintype "input"))
      (node (ref "U5") (pin "32") (pinfunction "GPIO21_32") (pintype "bidirectional"))
    )
    (net (code "3") (name "DAC_LDACN") (class "Default")
      (node (ref "J3") (pin "8") (pinfunction "8_8") (pintype "passive"))
      (node (ref "U3") (pin "4") (pinfunction "LDAC#_4") (pintype "input"))
      (node (ref "U5") (pin "29") (pinfunction "GPIO18_29") (pintype "bidirectional"))
    )
    (net (code "4") (name "DAC_MOSI") (class "Default")
      (node (ref "J3") (pin "6") (pinfunction "6_6") (pintype "passive"))
      (node (ref "U3") (pin "8") (pinfunction "SDIN_8") (pintype "input"))
      (node (ref "U5") (pin "35") (pinfunction "GPIO23_35") (pintype "bidirectional"))
    )
    (net (code "5") (name "DAC_RESETN") (class "Default")
      (node (ref "U3") (pin "3") (pinfunction "RESET#_3") (pintype "input"))
      (node (ref "U5") (pin "36") (pinfunction "GPIO24_36") (pintype "bidirectional"))
    )
    (net (code "6") (name "DAC_SCLK") (class "Default")
      (node (ref "J3") (pin "4") (pinfunction "4_4") (pintype "passive"))
      (node (ref "U3") (pin "6") (pinfunction "SCLK_6") (pintype "input"))
      (node (ref "U5") (pin "34") (pinfunction "GPIO22_34") (pintype "bidirectional"))
    )
    (net (code "7") (name "DUMMY_EN") (class "Default")
      (node (ref "J1") (pin "2") (pinfunction "2_2") (pintype "passive"))
      (node (ref "Q10") (pin "1") (pinfunction "S_1") (pintype "passive"))
      (node (ref "U5") (pin "28") (pinfunction "GPIO17_28") (pintype "bidirectional"))
    )
    (net (code "8") (name "GND") (class "Default")
      (node (ref "C1") (pin "2") (pinfunction "2_2") (pintype "passive"))
      (node (ref "C10") (pin "2") (pinfunction "2_2") (pintype "passive"))
      (node (ref "C11") (pin "2") (pinfunction "2_2") (pintype "passive"))
      (node (ref "C12") (pin "2") (pinfunction "2_2") (pintype "passive"))
      (node (ref "C13") (pin "2") (pinfunction "2_2") (pintype "passive"))
      (node (ref "C14") (pin "2") (pinfunction "2_2") (pintype "passive"))
      (node (ref "C15") (pin "2") (pinfunction "2_2") (pintype "passive"))
      (node (ref "C16") (pin "2") (pinfunction "2_2") (pintype "passive"))
      (node (ref "C17") (pin "2") (pinfunction "2_2") (pintype "passive"))
      (node (ref "C18") (pin "2") (pinfunction "2_2") (pintype "passive"))
      (node (ref "C19") (pin "2") (pinfunction "2_2") (pintype "passive"))
      (node (ref "C2") (pin "2") (pinfunction "2_2") (pintype "passive"))
      (node (ref "C20") (pin "N") (pinfunction "N_N") (pintype "passive"))
      (node (ref "C21") (pin "2") (pinfunction "2_2") (pintype "passive"))
      (node (ref "C22") (pin "2") (pinfunction "2_2") (pintype "passive"))
      (node (ref "C23") (pin "2") (pinfunction "2_2") (pintype "passive"))
      (node (ref "C24") (pin "1") (pinfunction "1_1") (pintype "passive"))
      (node (ref "C25") (pin "2") (pinfunction "2_2") (pintype "passive"))
      (node (ref "C26") (pin "2") (pinfunction "2_2") (pintype "passive"))
      (node (ref "C27") (pin "1") (pinfunction "1_1") (pintype "passive"))
      (node (ref "C28") (pin "2") (pinfunction "2_2") (pintype "passive"))
      (node (ref "C29") (pin "2") (pinfunction "2_2") (pintype "passive"))
      (node (ref "C3") (pin "2") (pinfunction "2_2") (pintype "passive"))
      (node (ref "C30") (pin "2") (pinfunction "2_2") (pintype "passive"))
      (node (ref "C31") (pin "2") (pinfunction "2_2") (pintype "passive"))
      (node (ref "C32") (pin "2") (pinfunction "2_2") (pintype "passive"))
      (node (ref "C33") (pin "2") (pinfunction "2_2") (pintype "passive"))
      (node (ref "C34") (pin "2") (pinfunction "2_2") (pintype "passive"))
      (node (ref "C35") (pin "2") (pinfunction "2_2") (pintype "passive"))
      (node (ref "C36") (pin "2") (pinfunction "2_2") (pintype "passive"))
      (node (ref "C37") (pin "2") (pinfunction "2_2") (pintype "passive"))
      (node (ref "C38") (pin "2") (pinfunction "2_2") (pintype "passive"))
      (node (ref "C39") (pin "2") (pinfunction "2_2") (pintype "passive"))
      (node (ref "C4") (pin "2") (pinfunction "2_2") (pintype "passive"))
      (node (ref "C40") (pin "2") (pinfunction "2_2") (pintype "passive"))
      (node (ref "C41") (pin "2") (pinfunction "2_2") (pintype "passive"))
      (node (ref "C42") (pin "2") (pinfunction "2_2") (pintype "passive"))
      (node (ref "C43") (pin "2") (pinfunction "2_2") (pintype "passive"))
      (node (ref "C44") (pin "2") (pinfunction "2_2") (pintype "passive"))
      (node (ref "C45") (pin "2") (pinfunction "2_2") (pintype "passive"))
      (node (ref "C46") (pin "2") (pinfunction "2_2") (pintype "passive"))
      (node (ref "C5") (pin "2") (pinfunction "2_2") (pintype "passive"))
      (node (ref "C6") (pin "2") (pinfunction "2_2") (pintype "passive"))
      (node (ref "C7") (pin "2") (pinfunction "2_2") (pintype "passive"))
      (node (ref "C8") (pin "2") (pinfunction "2_2") (pintype "passive"))
      (node (ref "D9") (pin "2") (pinfunction "A2_2") (pintype "bidirectional"))
      (node (ref "J1") (pin "1") (pinfunction "1_1") (pintype "passive"))
      (node (ref "J1") (pin "3") (pinfunction "3_3") (pintype "passive"))
      (node (ref "J1") (pin "5") (pinfunction "5_5") (pintype "passive"))
      (node (ref "J1") (pin "7") (pinfunction "7_7") (pintype "passive"))
      (node (ref "J2") (pin "25") (pinfunction "25_25") (pintype "passive"))
      (node (ref "J3") (pin "1") (pinfunction "1_1") (pintype "passive"))
      (node (ref "J3") (pin "3") (pinfunction "3_3") (pintype "passive"))
      (node (ref "J3") (pin "5") (pinfunction "5_5") (pintype "passive"))
      (node (ref "J3") (pin "7") (pinfunction "7_7") (pintype "passive"))
      (node (ref "J4") (pin "P$1") (pinfunction "GND_P$1") (pintype "bidirectional"))
      (node (ref "J4") (pin "P$2") (pinfunction "GND_P$2") (pintype "bidirectional"))
      (node (ref "J5") (pin "A10") (pinfunction "20_A10") (pintype "passive"))
      (node (ref "J5") (pin "A11") (pinfunction "22_A11") (pintype "passive"))
      (node (ref "J5") (pin "A12") (pinfunction "24_A12") (pintype "passive"))
      (node (ref "J5") (pin "A13") (pinfunction "26_A13") (pintype "passive"))
      (node (ref "J5") (pin "A14") (pinfunction "28_A14") (pintype "passive"))
      (node (ref "J5") (pin "A15") (pinfunction "30_A15") (pintype "passive"))
      (node (ref "J5") (pin "A16") (pinfunction "32_A16") (pintype "passive"))
      (node (ref "J5") (pin "A17") (pinfunction "34_A17") (pintype "passive"))
      (node (ref "J5") (pin "A2") (pinfunction "4_A2") (pintype "passive"))
      (node (ref "J5") (pin "A20") (pinfunction "40_A20") (pintype "passive"))
      (node (ref "J5") (pin "A4") (pinfunction "8_A4") (pintype "passive"))
      (node (ref "J5") (pin "A5") (pinfunction "10_A5") (pintype "passive"))
      (node (ref "J5") (pin "A6") (pinfunction "12_A6") (pintype "passive"))
      (node (ref "J5") (pin "A7") (pinfunction "14_A7") (pintype "passive"))
      (node (ref "J5") (pin "A8") (pinfunction "16_A8") (pintype "passive"))
      (node (ref "J5") (pin "A9") (pinfunction "18_A9") (pintype "passive"))
      (node (ref "J5") (pin "B18") (pinfunction "35_B18") (pintype "passive"))
      (node (ref "J5") (pin "B19") (pinfunction "37_B19") (pintype "passive"))
      (node (ref "J5") (pin "B2") (pinfunction "3_B2") (pintype "passive"))
      (node (ref "J5") (pin "B4") (pinfunction "7_B4") (pintype "passive"))
      (node (ref "J5") (pin "B8") (pinfunction "15_B8") (pintype "passive"))
      (node (ref "J6") (pin "2") (pinfunction "2_2") (pintype "passive"))
      (node (ref "J7") (pin "5") (pinfunction "5_5") (pintype "bidirectional"))
      (node (ref "J7") (pin "SH1") (pinfunction "SH1_SH1") (pintype "bidirectional"))
      (node (ref "J7") (pin "SH2") (pinfunction "SH2_SH2") (pintype "bidirectional"))
      (node (ref "J7") (pin "SH3") (pinfunction "SH3_SH3") (pintype "bidirectional"))
      (node (ref "J7") (pin "SH4") (pinfunction "SH4_SH4") (pintype "bidirectional"))
      (node (ref "J7") (pin "SH5") (pinfunction "SH5_SH5") (pintype "bidirectional"))
      (node (ref "J7") (pin "SH6") (pinfunction "SH6_SH6") (pintype "bidirectional"))
      (node (ref "LED1") (pin "C") (pinfunction "C_C") (pintype "passive"))
      (node (ref "LED2") (pin "C") (pinfunction "C_C") (pintype "passive"))
      (node (ref "Q9") (pin "1") (pinfunction "S_1") (pintype "passive"))
      (node (ref "Q9") (pin "2") (pinfunction "G_2") (pintype "passive"))
      (node (ref "Q9") (pin "6") (pinfunction "D_6") (pintype "passive"))
      (node (ref "Q9") (pin "P1") (pinfunction "D_P1") (pintype "passive"))
      (node (ref "R19") (pin "1") (pinfunction "1_1") (pintype "passive"))
      (node (ref "R26") (pin "1") (pinfunction "1_1") (pintype "passive"))
      (node (ref "R27") (pin "1") (pinfunction "1_1") (pintype "passive"))
      (node (ref "R28") (pin "1") (pinfunction "1_1") (pintype "passive"))
      (node (ref "R3") (pin "1") (pinfunction "1_1") (pintype "passive"))
      (node (ref "R8") (pin "1") (pinfunction "1_1") (pintype "passive"))
      (node (ref "S1") (pin "1") (pinfunction "1_1") (pintype "passive"))
      (node (ref "TP13") (pin "1") (pinfunction "P$1_1") (pintype "bidirectional"))
      (node (ref "U1") (pin "8") (pinfunction "GND_8") (pintype "power_in"))
      (node (ref "U10") (pin "1") (pinfunction "GND_1") (pintype "power_in"))
      (node (ref "U10") (pin "PAD") (pinfunction "GND_PAD") (pintype "power_in"))
      (node (ref "U2") (pin "4") (pinfunction "G2A#_4") (pintype "input"))
      (node (ref "U2") (pin "8") (pinfunction "GND_8") (pintype "power_in"))
      (node (ref "U3") (pin "5") (pinfunction "GND_5") (pintype "power_in"))
      (node (ref "U5") (pin "19") (pinfunction "TESTEN_19") (pintype "input"))
      (node (ref "U5") (pin "PAD") (pinfunction "GND_PAD") (pintype "power_in"))
      (node (ref "U6") (pin "4") (pinfunction "GND_4") (pintype "power_in"))
      (node (ref "U7") (pin "5") (pinfunction "GND_5") (pintype "bidirectional"))
      (node (ref "U8") (pin "4") (pinfunction "GND_4") (pintype "power_in"))
      (node (ref "U8") (pin "P") (pinfunction "GND_P") (pintype "power_in"))
      (node (ref "U9") (pin "1") (pinfunction "GND_1") (pintype "power_in"))
      (node (ref "U9") (pin "PAD") (pinfunction "GND_PAD") (pintype "power_in"))
      (node (ref "X1") (pin "2") (pinfunction "GND_2") (pintype "passive"))
      (node (ref "X1") (pin "4") (pinfunction "GND_4") (pintype "passive"))
    )
    (net (code "9") (name "GPIO00") (class "Default")
      (node (ref "J5") (pin "B15") (pinfunction "29_B15") (pintype "passive"))
      (node (ref "U5") (pin "2") (pinfunction "GPIO00_2") (pintype "bidirectional"))
    )
    (net (code "10") (name "GPIO01") (class "Default")
      (node (ref "J5") (pin "B14") (pinfunction "27_B14") (pintype "passive"))
      (node (ref "U5") (pin "3") (pinfunction "GPIO01_3") (pintype "bidirectional"))
    )
    (net (code "11") (name "GPIO02") (class "Default")
      (node (ref "J5") (pin "B13") (pinfunction "25_B13") (pintype "passive"))
      (node (ref "U5") (pin "4") (pinfunction "GPIO02_4") (pintype "bidirectional"))
    )
    (net (code "12") (name "GPIO03") (class "Default")
      (node (ref "J5") (pin "B12") (pinfunction "23_B12") (pintype "passive"))
      (node (ref "U5") (pin "5") (pinfunction "GPIO03_5") (pintype "bidirectional"))
    )
    (net (code "13") (name "GPIO04") (class "Default")
      (node (ref "J5") (pin "B11") (pinfunction "21_B11") (pintype "passive"))
      (node (ref "U5") (pin "6") (pinfunction "GPIO04_6") (pintype "bidirectional"))
    )
    (net (code "14") (name "GPIO05") (class "Default")
      (node (ref "J5") (pin "B10") (pinfunction "19_B10") (pintype "passive"))
      (node (ref "U5") (pin "7") (pinfunction "GPIO05_7") (pintype "bidirectional"))
    )
    (net (code "15") (name "GPIO06") (class "Default")
      (node (ref "J5") (pin "B9") (pinfunction "17_B9") (pintype "passive"))
      (node (ref "U5") (pin "8") (pinfunction "GPIO06_8") (pintype "bidirectional"))
    )
    (net (code "16") (name "LED0") (class "Default")
      (node (ref "R14") (pin "2") (pinfunction "2_2") (pintype "passive"))
      (node (ref "U5") (pin "11") (pinfunction "GPIO08_11") (pintype "bidirectional"))
    )
    (net (code "17") (name "LED1") (class "Default")
      (node (ref "R15") (pin "2") (pinfunction "2_2") (pintype "passive"))
      (node (ref "U5") (pin "9") (pinfunction "GPIO07_9") (pintype "bidirectional"))
    )
    (net (code "18") (name "LED_0A") (class "Default")
      (node (ref "D8") (pin "1") (pinfunction "A1_1") (pintype "bidirectional"))
      (node (ref "J2") (pin "1") (pinfunction "1_1") (pintype "passive"))
      (node (ref "Q4") (pin "6") (pinfunction "D_6") (pintype "passive"))
      (node (ref "Q4") (pin "P1") (pinfunction "D_P1") (pintype "passive"))
      (node (ref "TP1") (pin "P$1") (pinfunction "P$1_P$1") (pintype "bidirectional"))
    )
    (net (code "19") (name "LED_0B") (class "Default")
      (node (ref "D4") (pin "1") (pinfunction "A1_1") (pintype "bidirectional"))
      (node (ref "J2") (pin "4") (pinfunction "4_4") (pintype "passive"))
      (node (ref "Q4") (pin "3") (pinfunction "D_3") (pintype "passive"))
      (node (ref "Q4") (pin "P2") (pinfunction "D_P2") (pintype "passive"))
    )
    (net (code "20") (name "LED_1A") (class "Default")
      (node (ref "D4") (pin "2") (pinfunction "A2_2") (pintype "bidirectional"))
      (node (ref "J2") (pin "6") (pinfunction "6_6") (pintype "passive"))
      (node (ref "Q8") (pin "6") (pinfunction "D_6") (pintype "passive"))
      (node (ref "Q8") (pin "P1") (pinfunction "D_P1") (pintype "passive"))
    )
    (net (code "21") (name "LED_1B") (class "Default")
      (node (ref "D8") (pin "2") (pinfunction "A2_2") (pintype "bidirectional"))
      (node (ref "J2") (pin "5") (pinfunction "5_5") (pintype "passive"))
      (node (ref "Q8") (pin "3") (pinfunction "D_3") (pintype "passive"))
      (node (ref "Q8") (pin "P2") (pinfunction "D_P2") (pintype "passive"))
    )
    (net (code "22") (name "LED_2A") (class "Default")
      (node (ref "D7") (pin "1") (pinfunction "A1_1") (pintype "bidirectional"))
      (node (ref "J2") (pin "7") (pinfunction "7_7") (pintype "passive"))
      (node (ref "Q3") (pin "6") (pinfunction "D_6") (pintype "passive"))
      (node (ref "Q3") (pin "P1") (pinfunction "D_P1") (pintype "passive"))
    )
    (net (code "23") (name "LED_2B") (class "Default")
      (node (ref "D3") (pin "1") (pinfunction "A1_1") (pintype "bidirectional"))
      (node (ref "J2") (pin "10") (pinfunction "10_10") (pintype "passive"))
      (node (ref "Q3") (pin "3") (pinfunction "D_3") (pintype "passive"))
      (node (ref "Q3") (pin "P2") (pinfunction "D_P2") (pintype "passive"))
    )
    (net (code "24") (name "LED_3A") (class "Default")
      (node (ref "D3") (pin "2") (pinfunction "A2_2") (pintype "bidirectional"))
      (node (ref "J2") (pin "12") (pinfunction "12_12") (pintype "passive"))
      (node (ref "Q7") (pin "6") (pinfunction "D_6") (pintype "passive"))
      (node (ref "Q7") (pin "P1") (pinfunction "D_P1") (pintype "passive"))
    )
    (net (code "25") (name "LED_3B") (class "Default")
      (node (ref "D7") (pin "2") (pinfunction "A2_2") (pintype "bidirectional"))
      (node (ref "J2") (pin "11") (pinfunction "11_11") (pintype "passive"))
      (node (ref "Q7") (pin "3") (pinfunction "D_3") (pintype "passive"))
      (node (ref "Q7") (pin "P2") (pinfunction "D_P2") (pintype "passive"))
    )
    (net (code "26") (name "LED_4A") (class "Default")
      (node (ref "D6") (pin "1") (pinfunction "A1_1") (pintype "bidirectional"))
      (node (ref "J2") (pin "13") (pinfunction "13_13") (pintype "passive"))
      (node (ref "Q2") (pin "6") (pinfunction "D_6") (pintype "passive"))
      (node (ref "Q2") (pin "P1") (pinfunction "D_P1") (pintype "passive"))
    )
    (net (code "27") (name "LED_4B") (class "Default")
      (node (ref "D2") (pin "1") (pinfunction "A1_1") (pintype "bidirectional"))
      (node (ref "J2") (pin "16") (pinfunction "16_16") (pintype "passive"))
      (node (ref "Q2") (pin "3") (pinfunction "D_3") (pintype "passive"))
      (node (ref "Q2") (pin "P2") (pinfunction "D_P2") (pintype "passive"))
    )
    (net (code "28") (name "LED_5A") (class "Default")
      (node (ref "D2") (pin "2") (pinfunction "A2_2") (pintype "bidirectional"))
      (node (ref "J2") (pin "18") (pinfunction "18_18") (pintype "passive"))
      (node (ref "Q6") (pin "6") (pinfunction "D_6") (pintype "passive"))
      (node (ref "Q6") (pin "P1") (pinfunction "D_P1") (pintype "passive"))
    )
    (net (code "29") (name "LED_5B") (class "Default")
      (node (ref "D6") (pin "2") (pinfunction "A2_2") (pintype "bidirectional"))
      (node (ref "J2") (pin "17") (pinfunction "17_17") (pintype "passive"))
      (node (ref "Q6") (pin "3") (pinfunction "D_3") (pintype "passive"))
      (node (ref "Q6") (pin "P2") (pinfunction "D_P2") (pintype "passive"))
    )
    (net (code "30") (name "LED_6A") (class "Default")
      (node (ref "D5") (pin "1") (pinfunction "A1_1") (pintype "bidirectional"))
      (node (ref "J2") (pin "19") (pinfunction "19_19") (pintype "passive"))
      (node (ref "Q1") (pin "6") (pinfunction "D_6") (pintype "passive"))
      (node (ref "Q1") (pin "P1") (pinfunction "D_P1") (pintype "passive"))
    )
    (net (code "31") (name "LED_6B") (class "Default")
      (node (ref "D1") (pin "1") (pinfunction "A1_1") (pintype "bidirectional"))
      (node (ref "J2") (pin "22") (pinfunction "22_22") (pintype "passive"))
      (node (ref "Q1") (pin "3") (pinfunction "D_3") (pintype "passive"))
      (node (ref "Q1") (pin "P2") (pinfunction "D_P2") (pintype "passive"))
    )
    (net (code "32") (name "LED_7A") (class "Default")
      (node (ref "D1") (pin "2") (pinfunction "A2_2") (pintype "bidirectional"))
      (node (ref "J2") (pin "24") (pinfunction "24_24") (pintype "passive"))
      (node (ref "Q5") (pin "6") (pinfunction "D_6") (pintype "passive"))
      (node (ref "Q5") (pin "P1") (pinfunction "D_P1") (pintype "passive"))
    )
    (net (code "33") (name "LED_7B") (class "Default")
      (node (ref "D5") (pin "2") (pinfunction "A2_2") (pintype "bidirectional"))
      (node (ref "J2") (pin "23") (pinfunction "23_23") (pintype "passive"))
      (node (ref "Q5") (pin "3") (pinfunction "D_3") (pintype "passive"))
      (node (ref "Q5") (pin "P2") (pinfunction "D_P2") (pintype "passive"))
      (node (ref "TP2") (pin "P$1") (pinfunction "P$1_P$1") (pintype "bidirectional"))
    )
    (net (code "34") (name "LED_A") (class "Default")
      (node (ref "D1") (pin "3") (pinfunction "C_3") (pintype "bidirectional"))
      (node (ref "D2") (pin "3") (pinfunction "C_3") (pintype "bidirectional"))
      (node (ref "D3") (pin "3") (pinfunction "C_3") (pintype "bidirectional"))
      (node (ref "D4") (pin "3") (pinfunction "C_3") (pintype "bidirectional"))
      (node (ref "D5") (pin "3") (pinfunction "C_3") (pintype "bidirectional"))
      (node (ref "D6") (pin "3") (pinfunction "C_3") (pintype "bidirectional"))
      (node (ref "D7") (pin "3") (pinfunction "C_3") (pintype "bidirectional"))
      (node (ref "D8") (pin "3") (pinfunction "C_3") (pintype "bidirectional"))
      (node (ref "J2") (pin "14") (pinfunction "14_14") (pintype "passive"))
      (node (ref "J2") (pin "15") (pinfunction "15_15") (pintype "passive"))
      (node (ref "J2") (pin "2") (pinfunction "2_2") (pintype "passive"))
      (node (ref "J2") (pin "20") (pinfunction "20_20") (pintype "passive"))
      (node (ref "J2") (pin "21") (pinfunction "21_21") (pintype "passive"))
      (node (ref "J2") (pin "26") (pinfunction "26_26") (pintype "passive"))
      (node (ref "J2") (pin "3") (pinfunction "3_3") (pintype "passive"))
      (node (ref "J2") (pin "8") (pinfunction "8_8") (pintype "passive"))
      (node (ref "J2") (pin "9") (pinfunction "9_9") (pintype "passive"))
      (node (ref "R1") (pin "1") (pinfunction "1_1") (pintype "passive"))
    )
    (net (code "35") (name "LED_AD[0]") (class "Default")
      (node (ref "U1") (pin "1") (pinfunction "A_1") (pintype "input"))
      (node (ref "U2") (pin "1") (pinfunction "A_1") (pintype "input"))
      (node (ref "U5") (pin "15") (pinfunction "GPIO12_15") (pintype "bidirectional"))
    )
    (net (code "36") (name "LED_AD[1]") (class "Default")
      (node (ref "U1") (pin "2") (pinfunction "B_2") (pintype "input"))
      (node (ref "U2") (pin "2") (pinfunction "B_2") (pintype "input"))
      (node (ref "U5") (pin "16") (pinfunction "GPIO13_16") (pintype "bidirectional"))
    )
    (net (code "37") (name "LED_AD[2]") (class "Default")
      (node (ref "J1") (pin "8") (pinfunction "8_8") (pintype "passive"))
      (node (ref "U1") (pin "3") (pinfunction "C_3") (pintype "input"))
      (node (ref "U2") (pin "3") (pinfunction "C_3") (pintype "input"))
      (node (ref "U5") (pin "17") (pinfunction "GPIO14_17") (pintype "bidirectional"))
    )
    (net (code "38") (name "LED_AD[3]") (class "Default")
      (node (ref "J1") (pin "6") (pinfunction "6_6") (pintype "passive"))
      (node (ref "U1") (pin "4") (pinfunction "G2A#_4") (pintype "input"))
      (node (ref "U2") (pin "6") (pinfunction "G1_6") (pintype "input"))
      (node (ref "U5") (pin "18") (pinfunction "GPIO15_18") (pintype "bidirectional"))
    )
    (net (code "39") (name "LED_COM") (class "Default")
      (node (ref "Q1") (pin "1") (pinfunction "S_1") (pintype "passive"))
      (node (ref "Q1") (pin "4") (pinfunction "S_4") (pintype "passive"))
      (node (ref "Q10") (pin "4") (pinfunction "S_4") (pintype "passive"))
      (node (ref "Q2") (pin "1") (pinfunction "S_1") (pintype "passive"))
      (node (ref "Q2") (pin "4") (pinfunction "S_4") (pintype "passive"))
      (node (ref "Q3") (pin "1") (pinfunction "S_1") (pintype "passive"))
      (node (ref "Q3") (pin "4") (pinfunction "S_4") (pintype "passive"))
      (node (ref "Q4") (pin "1") (pinfunction "S_1") (pintype "passive"))
      (node (ref "Q4") (pin "4") (pinfunction "S_4") (pintype "passive"))
      (node (ref "Q5") (pin "1") (pinfunction "S_1") (pintype "passive"))
      (node (ref "Q5") (pin "4") (pinfunction "S_4") (pintype "passive"))
      (node (ref "Q6") (pin "1") (pinfunction "S_1") (pintype "passive"))
      (node (ref "Q6") (pin "4") (pinfunction "S_4") (pintype "passive"))
      (node (ref "Q7") (pin "1") (pinfunction "S_1") (pintype "passive"))
      (node (ref "Q7") (pin "4") (pinfunction "S_4") (pintype "passive"))
      (node (ref "Q8") (pin "1") (pinfunction "S_1") (pintype "passive"))
      (node (ref "Q8") (pin "4") (pinfunction "S_4") (pintype "passive"))
      (node (ref "Q9") (pin "3") (pinfunction "D_3") (pintype "passive"))
      (node (ref "Q9") (pin "P2") (pinfunction "D_P2") (pintype "passive"))
      (node (ref "R11") (pin "2") (pinfunction "2_2") (pintype "passive"))
      (node (ref "R13") (pin "2") (pinfunction "2_2") (pintype "passive"))
      (node (ref "R5") (pin "2") (pinfunction "2_2") (pintype "passive"))
      (node (ref "R9") (pin "2") (pinfunction "2_2") (pintype "passive"))
      (node (ref "TP15") (pin "P$1") (pinfunction "P$1_P$1") (pintype "bidirectional"))
    )
    (net (code "40") (name "LED_COM_SENSE") (class "Default")
      (node (ref "C13") (pin "1") (pinfunction "1_1") (pintype "passive"))
      (node (ref "R5") (pin "1") (pinfunction "1_1") (pintype "passive"))
      (node (ref "U5") (pin "41") (pinfunction "GPIO29/ADC3_41") (pintype "bidirectional"))
    )
    (net (code "41") (name "LED_CURR_SENSE") (class "Default")
      (node (ref "C14") (pin "1") (pinfunction "1_1") (pintype "passive"))
      (node (ref "R4") (pin "1") (pinfunction "1_1") (pintype "passive"))
      (node (ref "U5") (pin "38") (pinfunction "GPIO26/ADC0_38") (pintype "bidirectional"))
    )
    (net (code "42") (name "LED_ENN") (class "Default")
      (node (ref "J1") (pin "4") (pinfunction "4_4") (pintype "passive"))
      (node (ref "U1") (pin "5") (pinfunction "G2B#_5") (pintype "input"))
      (node (ref "U2") (pin "5") (pinfunction "G2B#_5") (pintype "input"))
      (node (ref "U5") (pin "27") (pinfunction "GPIO16_27") (pintype "bidirectional"))
    )
    (net (code "43") (name "Net-(C10-Pad1)") (class "Default")
      (node (ref "C10") (pin "1") (pinfunction "1_1") (pintype "passive"))
      (node (ref "R9") (pin "1") (pinfunction "1_1") (pintype "passive"))
    )
    (net (code "44") (name "Net-(C11-Pad1)") (class "Default")
      (node (ref "C11") (pin "1") (pinfunction "1_1") (pintype "passive"))
      (node (ref "R11") (pin "1") (pinfunction "1_1") (pintype "passive"))
    )
    (net (code "45") (name "Net-(C12-Pad1)") (class "Default")
      (node (ref "C12") (pin "1") (pinfunction "1_1") (pintype "passive"))
      (node (ref "R13") (pin "1") (pinfunction "1_1") (pintype "passive"))
    )
    (net (code "46") (name "Net-(J4-SIGNAL)") (class "Default")
      (node (ref "J4") (pin "P$3") (pinfunction "SIGNAL_P$3") (pintype "bidirectional"))
      (node (ref "R10") (pin "2") (pinfunction "2_2") (pintype "passive"))
    )
    (net (code "47") (name "Net-(J7-Pad2)") (class "Default")
      (node (ref "J7") (pin "2") (pinfunction "2_2") (pintype "bidirectional"))
      (node (ref "R25") (pin "2") (pinfunction "2_2") (pintype "passive"))
    )
    (net (code "48") (name "Net-(J7-Pad3)") (class "Default")
      (node (ref "J7") (pin "3") (pinfunction "3_3") (pintype "bidirectional"))
      (node (ref "R24") (pin "2") (pinfunction "2_2") (pintype "passive"))
    )
    (net (code "49") (name "Net-(LED1-PadA)") (class "Default")
      (node (ref "LED1") (pin "A") (pinfunction "A_A") (pintype "passive"))
      (node (ref "R14") (pin "1") (pinfunction "1_1") (pintype "passive"))
    )
    (net (code "50") (name "Net-(LED2-PadA)") (class "Default")
      (node (ref "LED2") (pin "A") (pinfunction "A_A") (pintype "passive"))
      (node (ref "R15") (pin "1") (pinfunction "1_1") (pintype "passive"))
    )
    (net (code "51") (name "Net-(Q1A-G)") (class "Default")
      (node (ref "Q1") (pin "2") (pinfunction "G_2") (pintype "passive"))
      (node (ref "U2") (pin "11") (pinfunction "Y4_11") (pintype "output"))
    )
    (net (code "52") (name "Net-(Q1B-G)") (class "Default")
      (node (ref "Q1") (pin "5") (pinfunction "G_5") (pintype "passive"))
      (node (ref "U2") (pin "10") (pinfunction "Y5_10") (pintype "output"))
    )
    (net (code "53") (name "Net-(Q2A-G)") (class "Default")
      (node (ref "Q2") (pin "2") (pinfunction "G_2") (pintype "passive"))
      (node (ref "U2") (pin "15") (pinfunction "Y0_15") (pintype "output"))
    )
    (net (code "54") (name "Net-(Q2B-G)") (class "Default")
      (node (ref "Q2") (pin "5") (pinfunction "G_5") (pintype "passive"))
      (node (ref "U2") (pin "14") (pinfunction "Y1_14") (pintype "output"))
    )
    (net (code "55") (name "Net-(Q3A-G)") (class "Default")
      (node (ref "Q3") (pin "2") (pinfunction "G_2") (pintype "passive"))
      (node (ref "U1") (pin "11") (pinfunction "Y4_11") (pintype "output"))
    )
    (net (code "56") (name "Net-(Q3B-G)") (class "Default")
      (node (ref "Q3") (pin "5") (pinfunction "G_5") (pintype "passive"))
      (node (ref "TP14") (pin "P$1") (pinfunction "P$1_P$1") (pintype "bidirectional"))
      (node (ref "U1") (pin "10") (pinfunction "Y5_10") (pintype "output"))
    )
    (net (code "57") (name "Net-(Q4A-G)") (class "Default")
      (node (ref "Q4") (pin "2") (pinfunction "G_2") (pintype "passive"))
      (node (ref "U1") (pin "15") (pinfunction "Y0_15") (pintype "output"))
    )
    (net (code "58") (name "Net-(Q4B-G)") (class "Default")
      (node (ref "Q4") (pin "5") (pinfunction "G_5") (pintype "passive"))
      (node (ref "U1") (pin "14") (pinfunction "Y1_14") (pintype "output"))
    )
    (net (code "59") (name "Net-(Q5A-G)") (class "Default")
      (node (ref "Q5") (pin "2") (pinfunction "G_2") (pintype "passive"))
      (node (ref "U2") (pin "9") (pinfunction "Y6_9") (pintype "output"))
    )
    (net (code "60") (name "Net-(Q5B-G)") (class "Default")
      (node (ref "Q5") (pin "5") (pinfunction "G_5") (pintype "passive"))
      (node (ref "U2") (pin "7") (pinfunction "Y7_7") (pintype "output"))
    )
    (net (code "61") (name "Net-(Q6A-G)") (class "Default")
      (node (ref "Q6") (pin "2") (pinfunction "G_2") (pintype "passive"))
      (node (ref "U2") (pin "13") (pinfunction "Y2_13") (pintype "output"))
    )
    (net (code "62") (name "Net-(Q6B-G)") (class "Default")
      (node (ref "Q6") (pin "5") (pinfunction "G_5") (pintype "passive"))
      (node (ref "U2") (pin "12") (pinfunction "Y3_12") (pintype "output"))
    )
    (net (code "63") (name "Net-(Q7A-G)") (class "Default")
      (node (ref "Q7") (pin "2") (pinfunction "G_2") (pintype "passive"))
      (node (ref "U1") (pin "9") (pinfunction "Y6_9") (pintype "output"))
    )
    (net (code "64") (name "Net-(Q7B-G)") (class "Default")
      (node (ref "Q7") (pin "5") (pinfunction "G_5") (pintype "passive"))
      (node (ref "U1") (pin "7") (pinfunction "Y7_7") (pintype "output"))
    )
    (net (code "65") (name "Net-(Q8A-G)") (class "Default")
      (node (ref "Q8") (pin "2") (pinfunction "G_2") (pintype "passive"))
      (node (ref "U1") (pin "13") (pinfunction "Y2_13") (pintype "output"))
    )
    (net (code "66") (name "Net-(Q8B-G)") (class "Default")
      (node (ref "Q8") (pin "5") (pinfunction "G_5") (pintype "passive"))
      (node (ref "U1") (pin "12") (pinfunction "Y3_12") (pintype "output"))
    )
    (net (code "67") (name "Net-(Q9B-G)") (class "Default")
      (node (ref "Q9") (pin "5") (pinfunction "G_5") (pintype "passive"))
      (node (ref "R6") (pin "2") (pinfunction "2_2") (pintype "passive"))
    )
    (net (code "68") (name "Net-(Q9B-S)") (class "Default")
      (node (ref "Q9") (pin "4") (pinfunction "S_4") (pintype "passive"))
      (node (ref "R10") (pin "1") (pinfunction "1_1") (pintype "passive"))
      (node (ref "R4") (pin "2") (pinfunction "2_2") (pintype "passive"))
      (node (ref "R7") (pin "2") (pinfunction "2_2") (pintype "passive"))
      (node (ref "R8") (pin "2") (pinfunction "2_2") (pintype "passive"))
      (node (ref "TP4") (pin "P$1") (pinfunction "P$1_P$1") (pintype "bidirectional"))
    )
    (net (code "69") (name "Net-(Q10B-D-Pad3)") (class "Default")
      (node (ref "Q10") (pin "3") (pinfunction "D_3") (pintype "passive"))
      (node (ref "Q10") (pin "P2") (pinfunction "D_P2") (pintype "passive"))
      (node (ref "R12") (pin "1") (pinfunction "1_1") (pintype "passive"))
    )
    (net (code "70") (name "Net-(Q10B-G)") (class "Default")
      (node (ref "Q10") (pin "5") (pinfunction "G_5") (pintype "passive"))
      (node (ref "Q10") (pin "6") (pinfunction "D_6") (pintype "passive"))
      (node (ref "Q10") (pin "P1") (pinfunction "D_P1") (pintype "passive"))
      (node (ref "R32") (pin "1") (pinfunction "1_1") (pintype "passive"))
    )
    (net (code "71") (name "Net-(U3-VOUT)") (class "Default")
      (node (ref "R2") (pin "1") (pinfunction "1_1") (pintype "passive"))
      (node (ref "U3") (pin "10") (pinfunction "VOUT_10") (pintype "output"))
    )
    (net (code "72") (name "Net-(U3-VREF)") (class "Default")
      (node (ref "C4") (pin "1") (pinfunction "1_1") (pintype "passive"))
      (node (ref "U3") (pin "9") (pinfunction "VREF_9") (pintype "bidirectional"))
    )
    (net (code "73") (name "Net-(U4-+IN)") (class "Default")
      (node (ref "C6") (pin "1") (pinfunction "1_1") (pintype "passive"))
      (node (ref "R2") (pin "2") (pinfunction "2_2") (pintype "passive"))
      (node (ref "R3") (pin "2") (pinfunction "2_2") (pintype "passive"))
      (node (ref "TP3") (pin "P$1") (pinfunction "P$1_P$1") (pintype "bidirectional"))
      (node (ref "U4") (pin "3") (pinfunction "+IN_3") (pintype "input"))
    )
    (net (code "74") (name "Net-(U4--IN)") (class "Default")
      (node (ref "C9") (pin "2") (pinfunction "2_2") (pintype "passive"))
      (node (ref "R7") (pin "1") (pinfunction "1_1") (pintype "passive"))
      (node (ref "U4") (pin "4") (pinfunction "-IN_4") (pintype "input"))
    )
    (net (code "75") (name "Net-(U4-OUT)") (class "Default")
      (node (ref "C9") (pin "1") (pinfunction "1_1") (pintype "passive"))
      (node (ref "R6") (pin "1") (pinfunction "1_1") (pintype "passive"))
      (node (ref "U4") (pin "1") (pinfunction "OUT_1") (pintype "output"))
    )
    (net (code "76") (name "Net-(U5B-SWCLK)") (class "Default")
      (node (ref "R33") (pin "1") (pinfunction "1_1") (pintype "passive"))
      (node (ref "U5") (pin "24") (pinfunction "SWCLK_24") (pintype "input"))
    )
    (net (code "77") (name "Net-(U5B-SWDIO)") (class "Default")
      (node (ref "R34") (pin "1") (pinfunction "1_1") (pintype "passive"))
      (node (ref "U5") (pin "25") (pinfunction "SWDIO_25") (pintype "bidirectional"))
    )
    (net (code "78") (name "Net-(U5B-USB_DN)") (class "Default")
      (node (ref "R25") (pin "1") (pinfunction "1_1") (pintype "passive"))
      (node (ref "U5") (pin "46") (pinfunction "USB_DN_46") (pintype "bidirectional"))
    )
    (net (code "79") (name "Net-(U5B-USB_DP)") (class "Default")
      (node (ref "R24") (pin "1") (pinfunction "1_1") (pintype "passive"))
      (node (ref "U5") (pin "47") (pinfunction "USB_DP_47") (pintype "bidirectional"))
    )
    (net (code "80") (name "Net-(U5B-XIN)") (class "Default")
      (node (ref "C19") (pin "1") (pinfunction "1_1") (pintype "passive"))
      (node (ref "U5") (pin "20") (pinfunction "XIN_20") (pintype "bidirectional"))
      (node (ref "X1") (pin "3") (pinfunction "C2_3") (pintype "passive"))
    )
    (net (code "81") (name "Net-(U5B-XOUT)") (class "Default")
      (node (ref "R23") (pin "1") (pinfunction "1_1") (pintype "passive"))
      (node (ref "U5") (pin "21") (pinfunction "XOUT_21") (pintype "bidirectional"))
    )
    (net (code "82") (name "Net-(U5C-ADC_VDD)") (class "Default")
      (node (ref "C40") (pin "1") (pinfunction "1_1") (pintype "passive"))
      (node (ref "R31") (pin "2") (pinfunction "2_2") (pintype "passive"))
      (node (ref "U5") (pin "43") (pinfunction "ADC_VDD_43") (pintype "power_in"))
    )
    (net (code "83") (name "Net-(U9-ADJ{slash}SENSE)") (class "Default")
      (node (ref "R27") (pin "2") (pinfunction "2_2") (pintype "passive"))
      (node (ref "R29") (pin "1") (pinfunction "1_1") (pintype "passive"))
      (node (ref "U9") (pin "2") (pinfunction "ADJ/SENSE_2") (pintype "input"))
    )
    (net (code "84") (name "Net-(U10-ADJ{slash}SENSE)") (class "Default")
      (node (ref "R28") (pin "2") (pinfunction "2_2") (pintype "passive"))
      (node (ref "R30") (pin "1") (pinfunction "1_1") (pintype "passive"))
      (node (ref "U10") (pin "2") (pinfunction "ADJ/SENSE_2") (pintype "input"))
    )
    (net (code "85") (name "Net-(X1-C1)") (class "Default")
      (node (ref "C18") (pin "1") (pinfunction "1_1") (pintype "passive"))
      (node (ref "R23") (pin "2") (pinfunction "2_2") (pintype "passive"))
      (node (ref "X1") (pin "1") (pinfunction "C1_1") (pintype "passive"))
    )
    (net (code "86") (name "QSPI_SCLK") (class "Default")
      (node (ref "U5") (pin "52") (pinfunction "QSPI_SCLK_52") (pintype "output"))
      (node (ref "U6") (pin "6") (pinfunction "CLK_6") (pintype "input"))
    )
    (net (code "87") (name "QSPI_SD0") (class "Default")
      (node (ref "U5") (pin "53") (pinfunction "QSPI_SD0_53") (pintype "bidirectional"))
      (node (ref "U6") (pin "5") (pinfunction "DI/IO[0]_5") (pintype "bidirectional"))
    )
    (net (code "88") (name "QSPI_SD1") (class "Default")
      (node (ref "U5") (pin "55") (pinfunction "QSPI_SD1_55") (pintype "bidirectional"))
      (node (ref "U6") (pin "2") (pinfunction "DO/IO[1]_2") (pintype "bidirectional"))
    )
    (net (code "89") (name "QSPI_SD2") (class "Default")
      (node (ref "U5") (pin "54") (pinfunction "QSPI_SD2_54") (pintype "bidirectional"))
      (node (ref "U6") (pin "3") (pinfunction "#WP/IO[2]_3") (pintype "bidirectional"))
    )
    (net (code "90") (name "QSPI_SD3") (class "Default")
      (node (ref "U5") (pin "51") (pinfunction "QSPI_SD3_51") (pintype "bidirectional"))
      (node (ref "U6") (pin "7") (pinfunction "#HOLD/IO[3]_7") (pintype "bidirectional"))
    )
    (net (code "91") (name "QSPI_SS_N") (class "Default")
      (node (ref "R20") (pin "2") (pinfunction "2_2") (pintype "passive"))
      (node (ref "R22") (pin "1") (pinfunction "1_1") (pintype "passive"))
      (node (ref "U5") (pin "56") (pinfunction "QSPI_SS_N_56") (pintype "output"))
      (node (ref "U6") (pin "1") (pinfunction "/CS_1") (pintype "input"))
    )
    (net (code "92") (name "RUN") (class "Default")
      (node (ref "J5") (pin "B7") (pinfunction "13_B7") (pintype "passive"))
      (node (ref "R21") (pin "1") (pinfunction "1_1") (pintype "passive"))
      (node (ref "U5") (pin "26") (pinfunction "RUN_26") (pintype "input"))
    )
    (net (code "93") (name "SPARE0") (class "Default")
      (node (ref "TP5") (pin "P$1") (pinfunction "P$1_P$1") (pintype "bidirectional"))
      (node (ref "U5") (pin "30") (pinfunction "GPIO19_30") (pintype "bidirectional"))
    )
    (net (code "94") (name "SPARE1") (class "Default")
      (node (ref "TP6") (pin "P$1") (pinfunction "P$1_P$1") (pintype "bidirectional"))
      (node (ref "U5") (pin "31") (pinfunction "GPIO20_31") (pintype "bidirectional"))
    )
    (net (code "95") (name "SWCLK") (class "Default")
      (node (ref "J5") (pin "B6") (pinfunction "11_B6") (pintype "passive"))
      (node (ref "J6") (pin "1") (pinfunction "1_1") (pintype "passive"))
      (node (ref "R33") (pin "2") (pinfunction "2_2") (pintype "passive"))
    )
    (net (code "96") (name "SWDIO") (class "Default")
      (node (ref "J5") (pin "B5") (pinfunction "9_B5") (pintype "passive"))
      (node (ref "J6") (pin "3") (pinfunction "3_3") (pintype "passive"))
      (node (ref "R34") (pin "2") (pinfunction "2_2") (pintype "passive"))
    )
    (net (code "97") (name "V1P1") (class "Default")
      (node (ref "C33") (pin "1") (pinfunction "1_1") (pintype "passive"))
      (node (ref "C34") (pin "1") (pinfunction "1_1") (pintype "passive"))
      (node (ref "C35") (pin "1") (pinfunction "1_1") (pintype "passive"))
      (node (ref "TP12") (pin "P$1") (pinfunction "P$1_P$1") (pintype "bidirectional"))
      (node (ref "U5") (pin "23") (pinfunction "DVDD_23") (pintype "power_in"))
      (node (ref "U5") (pin "45") (pinfunction "VREG_VOUT_45") (pintype "power_in"))
      (node (ref "U5") (pin "50") (pinfunction "DVDD_50") (pintype "power_in"))
    )
    (net (code "98") (name "V3P3") (class "Default")
      (node (ref "C17") (pin "1") (pinfunction "1_1") (pintype "passive"))
      (node (ref "C26") (pin "1") (pinfunction "1_1") (pintype "passive"))
      (node (ref "C28") (pin "1") (pinfunction "1_1") (pintype "passive"))
      (node (ref "C36") (pin "1") (pinfunction "1_1") (pintype "passive"))
      (node (ref "C37") (pin "1") (pinfunction "1_1") (pintype "passive"))
      (node (ref "C38") (pin "1") (pinfunction "1_1") (pintype "passive"))
      (node (ref "C39") (pin "1") (pinfunction "1_1") (pintype "passive"))
      (node (ref "C41") (pin "1") (pinfunction "1_1") (pintype "passive"))
      (node (ref "C42") (pin "1") (pinfunction "1_1") (pintype "passive"))
      (node (ref "C43") (pin "1") (pinfunction "1_1") (pintype "passive"))
      (node (ref "C5") (pin "1") (pinfunction "1_1") (pintype "passive"))
      (node (ref "J5") (pin "B16") (pinfunction "31_B16") (pintype "passive"))
      (node (ref "Q10") (pin "2") (pinfunction "G_2") (pintype "passive"))
      (node (ref "R16") (pin "2") (pinfunction "2_2") (pintype "passive"))
      (node (ref "R21") (pin "2") (pinfunction "2_2") (pintype "passive"))
      (node (ref "R22") (pin "2") (pinfunction "2_2") (pintype "passive"))
      (node (ref "R31") (pin "1") (pinfunction "1_1") (pintype "passive"))
      (node (ref "TP8") (pin "P$1") (pinfunction "P$1_P$1") (pintype "bidirectional"))
      (node (ref "U3") (pin "2") (pinfunction "VLOGIC_2") (pintype "power_in"))
      (node (ref "U5") (pin "1") (pinfunction "IOVDD_1") (pintype "power_in"))
      (node (ref "U5") (pin "10") (pinfunction "IOVDD_10") (pintype "power_in"))
      (node (ref "U5") (pin "22") (pinfunction "IOVDD_22") (pintype "power_in"))
      (node (ref "U5") (pin "33") (pinfunction "IOVDD_33") (pintype "power_in"))
      (node (ref "U5") (pin "42") (pinfunction "IOVDD_42") (pintype "power_in"))
      (node (ref "U5") (pin "44") (pinfunction "VREG_VIN_44") (pintype "power_in"))
      (node (ref "U5") (pin "48") (pinfunction "USB_VDD_48") (pintype "power_in"))
      (node (ref "U5") (pin "49") (pinfunction "IOVDD_49") (pintype "power_in"))
      (node (ref "U6") (pin "8") (pinfunction "VCC_8") (pintype "power_in"))
      (node (ref "U8") (pin "1") (pinfunction "OUT_1") (pintype "power_in"))
    )
    (net (code "99") (name "V4P0") (class "Default")
      (node (ref "C1") (pin "1") (pinfunction "1_1") (pintype "passive"))
      (node (ref "C2") (pin "1") (pinfunction "1_1") (pintype "passive"))
      (node (ref "C29") (pin "1") (pinfunction "1_1") (pintype "passive"))
      (node (ref "C3") (pin "1") (pinfunction "1_1") (pintype "passive"))
      (node (ref "C31") (pin "1") (pinfunction "1_1") (pintype "passive"))
      (node (ref "C7") (pin "1") (pinfunction "1_1") (pintype "passive"))
      (node (ref "R29") (pin "2") (pinfunction "2_2") (pintype "passive"))
      (node (ref "R32") (pin "2") (pinfunction "2_2") (pintype "passive"))
      (node (ref "TP10") (pin "P$1") (pinfunction "P$1_P$1") (pintype "bidirectional"))
      (node (ref "U1") (pin "16") (pinfunction "VCC_16") (pintype "power_in"))
      (node (ref "U1") (pin "6") (pinfunction "G1_6") (pintype "input"))
      (node (ref "U2") (pin "16") (pinfunction "VCC_16") (pintype "power_in"))
      (node (ref "U3") (pin "1") (pinfunction "VDD_1") (pintype "power_in"))
      (node (ref "U4") (pin "5") (pinfunction "V+_5") (pintype "power_in"))
      (node (ref "U9") (pin "3") (pinfunction "VOUT_3") (pintype "power_in"))
    )
    (net (code "100") (name "VBUS") (class "Default")
      (node (ref "D10") (pin "1") (pinfunction "A1_1") (pintype "bidirectional"))
      (node (ref "D10") (pin "2") (pinfunction "A2_2") (pintype "bidirectional"))
      (node (ref "J7") (pin "1") (pinfunction "1_1") (pintype "bidirectional"))
    )
    (net (code "101") (name "VIN") (class "Default")
      (node (ref "D11") (pin "1") (pinfunction "A1_1") (pintype "bidirectional"))
      (node (ref "D11") (pin "2") (pinfunction "A2_2") (pintype "bidirectional"))
      (node (ref "F1") (pin "2") (pinfunction "2_2") (pintype "bidirectional"))
      (node (ref "J5") (pin "A1") (pinfunction "2_A1") (pintype "passive"))
      (node (ref "J5") (pin "A3") (pinfunction "6_A3") (pintype "passive"))
      (node (ref "J5") (pin "B1") (pinfunction "1_B1") (pintype "passive"))
      (node (ref "J5") (pin "B3") (pinfunction "5_B3") (pintype "passive"))
    )
    (net (code "102") (name "VIN_F") (class "Default")
      (node (ref "C20") (pin "P") (pinfunction "P_P") (pintype "passive"))
      (node (ref "C21") (pin "1") (pinfunction "1_1") (pintype "passive"))
      (node (ref "C23") (pin "1") (pinfunction "1_1") (pintype "passive"))
      (node (ref "C44") (pin "1") (pinfunction "1_1") (pintype "passive"))
      (node (ref "C45") (pin "1") (pinfunction "1_1") (pintype "passive"))
      (node (ref "F1") (pin "1") (pinfunction "1_1") (pintype "bidirectional"))
      (node (ref "R18") (pin "2") (pinfunction "2_2") (pintype "passive"))
      (node (ref "U10") (pin "4") (pinfunction "VIN_4") (pintype "power_in"))
      (node (ref "U9") (pin "4") (pinfunction "VIN_4") (pintype "power_in"))
      (node (ref "U9") (pin "6") (pinfunction "EN_6") (pintype "input"))
    )
    (net (code "103") (name "VIN_MCU") (class "Default")
      (node (ref "C22") (pin "1") (pinfunction "1_1") (pintype "passive"))
      (node (ref "C25") (pin "1") (pinfunction "1_1") (pintype "passive"))
      (node (ref "D10") (pin "3") (pinfunction "C_3") (pintype "bidirectional"))
      (node (ref "D11") (pin "3") (pinfunction "C_3") (pintype "bidirectional"))
      (node (ref "TP7") (pin "P$1") (pinfunction "P$1_P$1") (pintype "bidirectional"))
      (node (ref "U8") (pin "5") (pinfunction "/SHDN_5") (pintype "input"))
      (node (ref "U8") (pin "8") (pinfunction "IN_8") (pintype "power_in"))
    )
    (net (code "104") (name "VIN_SENSE") (class "Default")
      (node (ref "C16") (pin "1") (pinfunction "1_1") (pintype "passive"))
      (node (ref "R18") (pin "1") (pinfunction "1_1") (pintype "passive"))
      (node (ref "R19") (pin "2") (pinfunction "2_2") (pintype "passive"))
      (node (ref "U5") (pin "39") (pinfunction "GPIO27/ADC1_39") (pintype "bidirectional"))
    )
    (net (code "105") (name "VLED") (class "Default")
      (node (ref "C30") (pin "1") (pinfunction "1_1") (pintype "passive"))
      (node (ref "C32") (pin "1") (pinfunction "1_1") (pintype "passive"))
      (node (ref "C46") (pin "1") (pinfunction "1_1") (pintype "passive"))
      (node (ref "R1") (pin "2") (pinfunction "2_2") (pintype "passive"))
      (node (ref "R12") (pin "2") (pinfunction "2_2") (pintype "passive"))
      (node (ref "R30") (pin "2") (pinfunction "2_2") (pintype "passive"))
      (node (ref "TP11") (pin "P$1") (pinfunction "P$1_P$1") (pintype "bidirectional"))
      (node (ref "U10") (pin "3") (pinfunction "VOUT_3") (pintype "power_in"))
    )
    (net (code "106") (name "VLED_EN") (class "Default")
      (node (ref "R26") (pin "2") (pinfunction "2_2") (pintype "passive"))
      (node (ref "U10") (pin "6") (pinfunction "EN_6") (pintype "input"))
      (node (ref "U5") (pin "13") (pinfunction "GPIO10_13") (pintype "bidirectional"))
    )
    (net (code "107") (name "VN1P2") (class "Default")
      (node (ref "C27") (pin "2") (pinfunction "2_2") (pintype "passive"))
      (node (ref "C8") (pin "1") (pinfunction "1_1") (pintype "passive"))
      (node (ref "TP9") (pin "P$1") (pinfunction "P$1_P$1") (pintype "bidirectional"))
      (node (ref "U4") (pin "2") (pinfunction "V-_2") (pintype "power_in"))
      (node (ref "U7") (pin "1") (pinfunction "OUT_1") (pintype "bidirectional"))
      (node (ref "U7") (pin "2") (pinfunction "NC/ADJ_2") (pintype "bidirectional"))
    )
    (net (code "108") (name "VN3P0") (class "Default")
      (node (ref "C24") (pin "2") (pinfunction "2_2") (pintype "passive"))
      (node (ref "J5") (pin "A19") (pinfunction "38_A19") (pintype "passive"))
      (node (ref "R17") (pin "1") (pinfunction "1_1") (pintype "passive"))
      (node (ref "U7") (pin "3") (pinfunction "EN_3") (pintype "bidirectional"))
      (node (ref "U7") (pin "6") (pinfunction "IN_6") (pintype "bidirectional"))
      (node (ref "U7") (pin "PAD") (pinfunction "IN_PAD") (pintype "bidirectional"))
    )
    (net (code "109") (name "VN3P0_SENSE") (class "Default")
      (node (ref "C15") (pin "1") (pinfunction "1_1") (pintype "passive"))
      (node (ref "D9") (pin "3") (pinfunction "C_3") (pintype "bidirectional"))
      (node (ref "R16") (pin "1") (pinfunction "1_1") (pintype "passive"))
      (node (ref "R17") (pin "2") (pinfunction "2_2") (pintype "passive"))
      (node (ref "U5") (pin "40") (pinfunction "GPIO28/ADC2_40") (pintype "bidirectional"))
    )
    (net (code "110") (name "unconnected-(D9-A1-Pad1)") (class "Default")
      (node (ref "D9") (pin "1") (pinfunction "A1_1") (pintype "bidirectional"))
    )
    (net (code "111") (name "unconnected-(J5-36-PadA18)") (class "Default")
      (node (ref "J5") (pin "A18") (pinfunction "36_A18") (pintype "passive"))
    )
    (net (code "112") (name "unconnected-(J5-39-PadB20)") (class "Default")
      (node (ref "J5") (pin "B20") (pinfunction "39_B20") (pintype "passive"))
    )
    (net (code "113") (name "unconnected-(J7-Pad4)") (class "Default")
      (node (ref "J7") (pin "4") (pinfunction "4_4") (pintype "bidirectional"))
    )
    (net (code "114") (name "unconnected-(U5A-GPIO09-Pad12)") (class "Default")
      (node (ref "U5") (pin "12") (pinfunction "GPIO09_12") (pintype "bidirectional"))
    )
    (net (code "115") (name "unconnected-(U5A-GPIO11-Pad14)") (class "Default")
      (node (ref "U5") (pin "14") (pinfunction "GPIO11_14") (pintype "bidirectional"))
    )
    (net (code "116") (name "unconnected-(U5A-GPIO25-Pad37)") (class "Default")
      (node (ref "U5") (pin "37") (pinfunction "GPIO25_37") (pintype "bidirectional"))
    )
    (net (code "117") (name "unconnected-(U8-PWRGD-Pad2)") (class "Default")
      (node (ref "U8") (pin "2") (pinfunction "PWRGD_2") (pintype "output"))
    )
  )
)
